# mcat-4cu-b-v2h.net
KiCad netlist of a schematic drawn in EAGLE
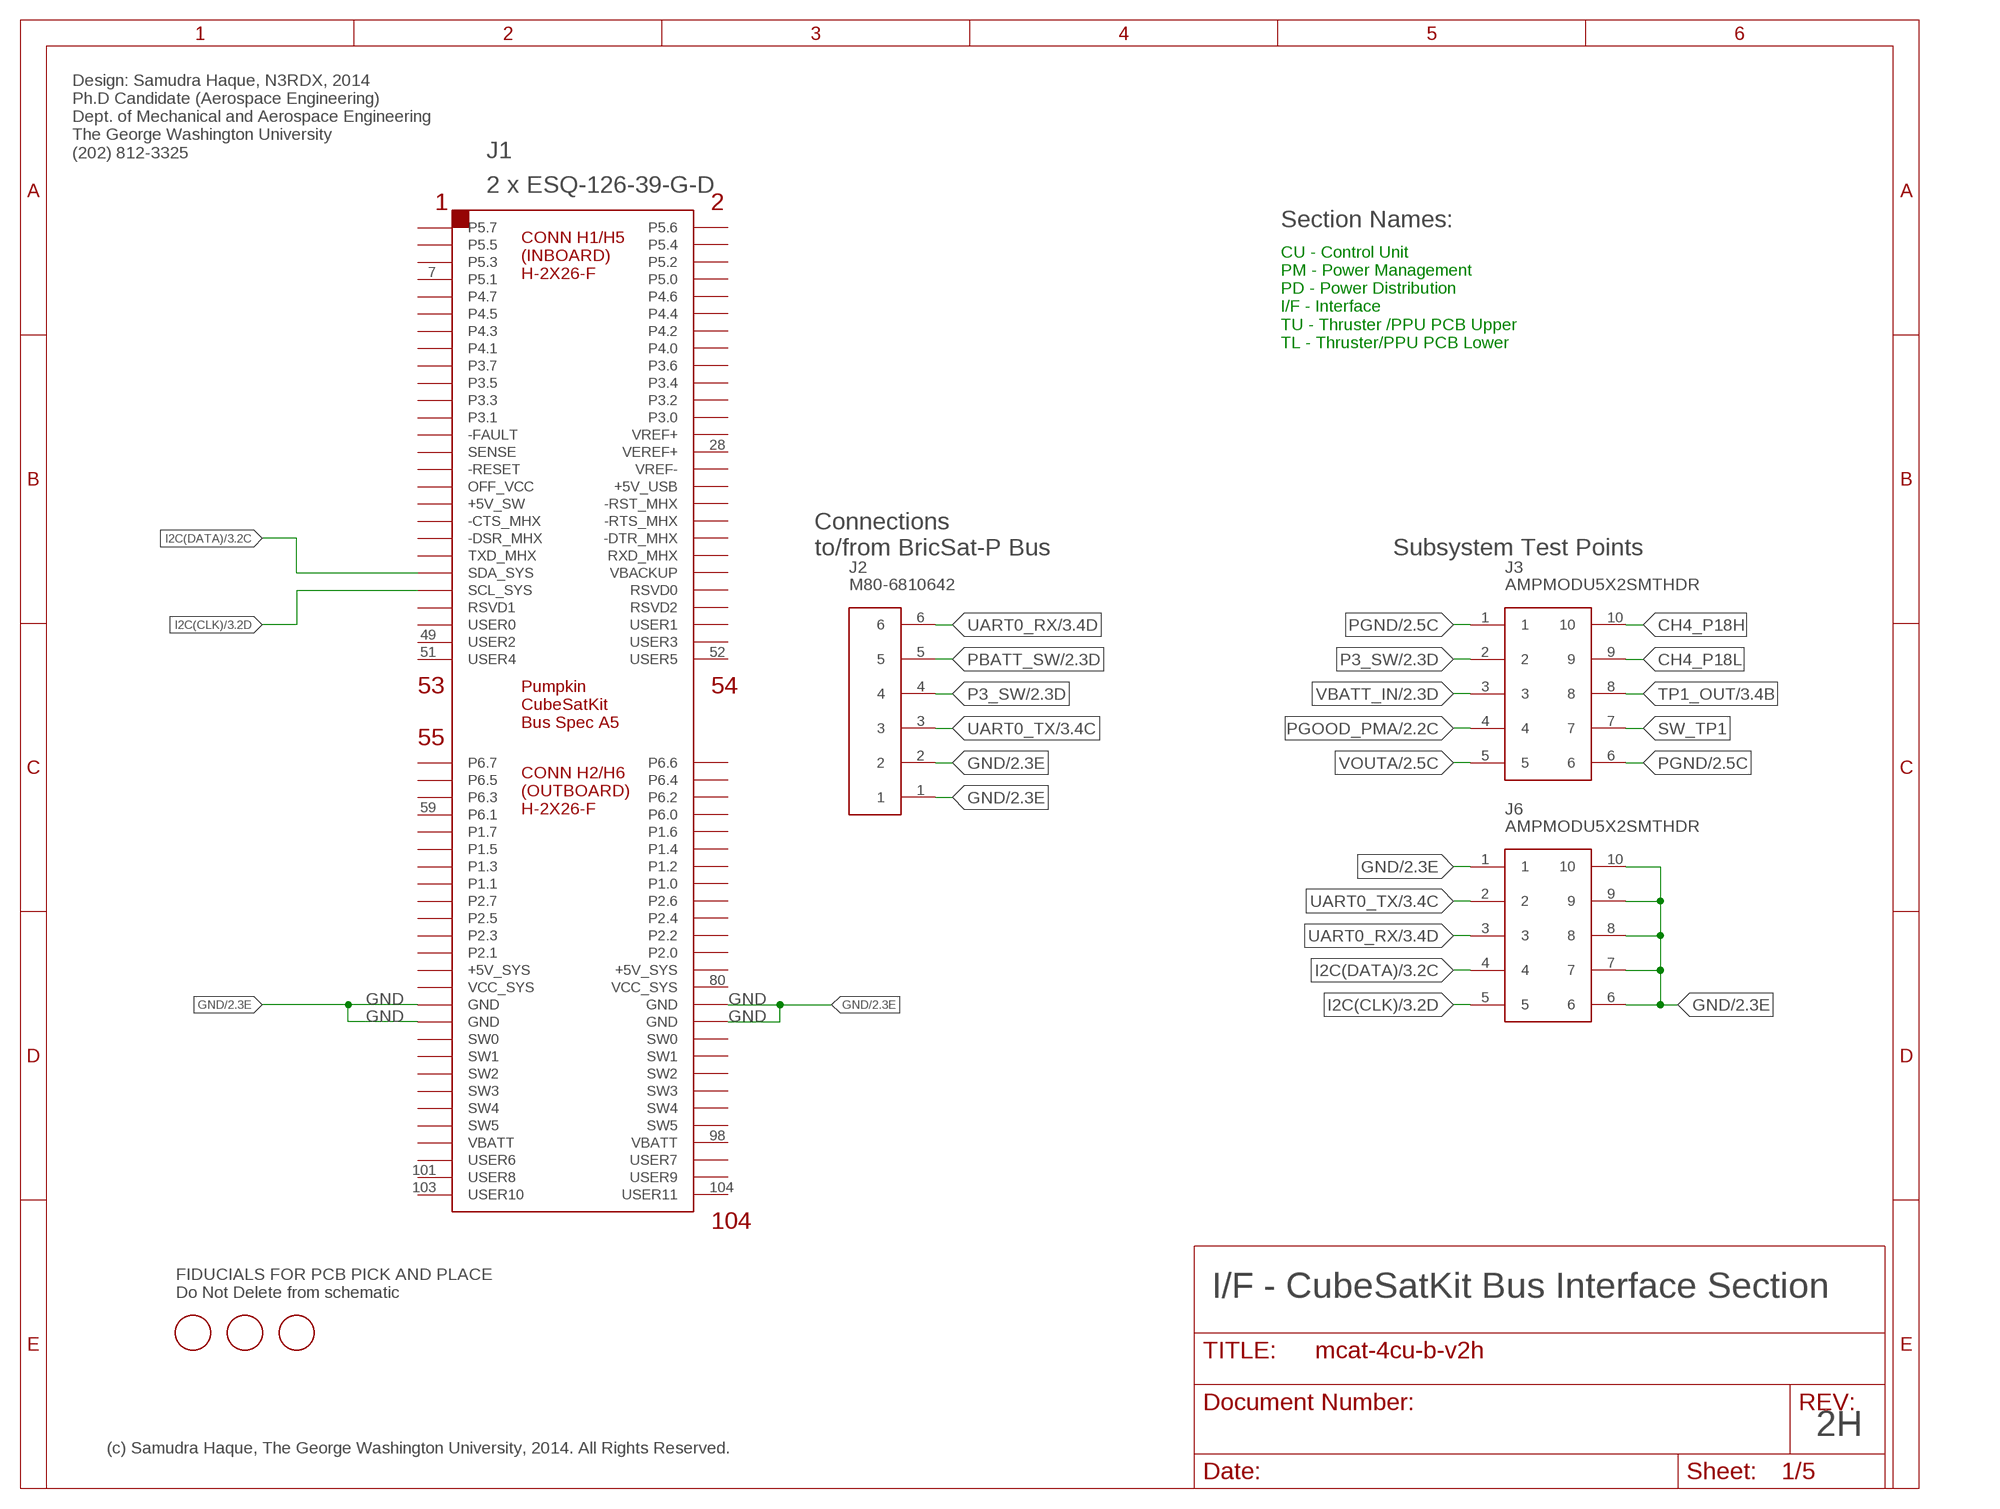
[diagram p0: schematic, sheet 1]
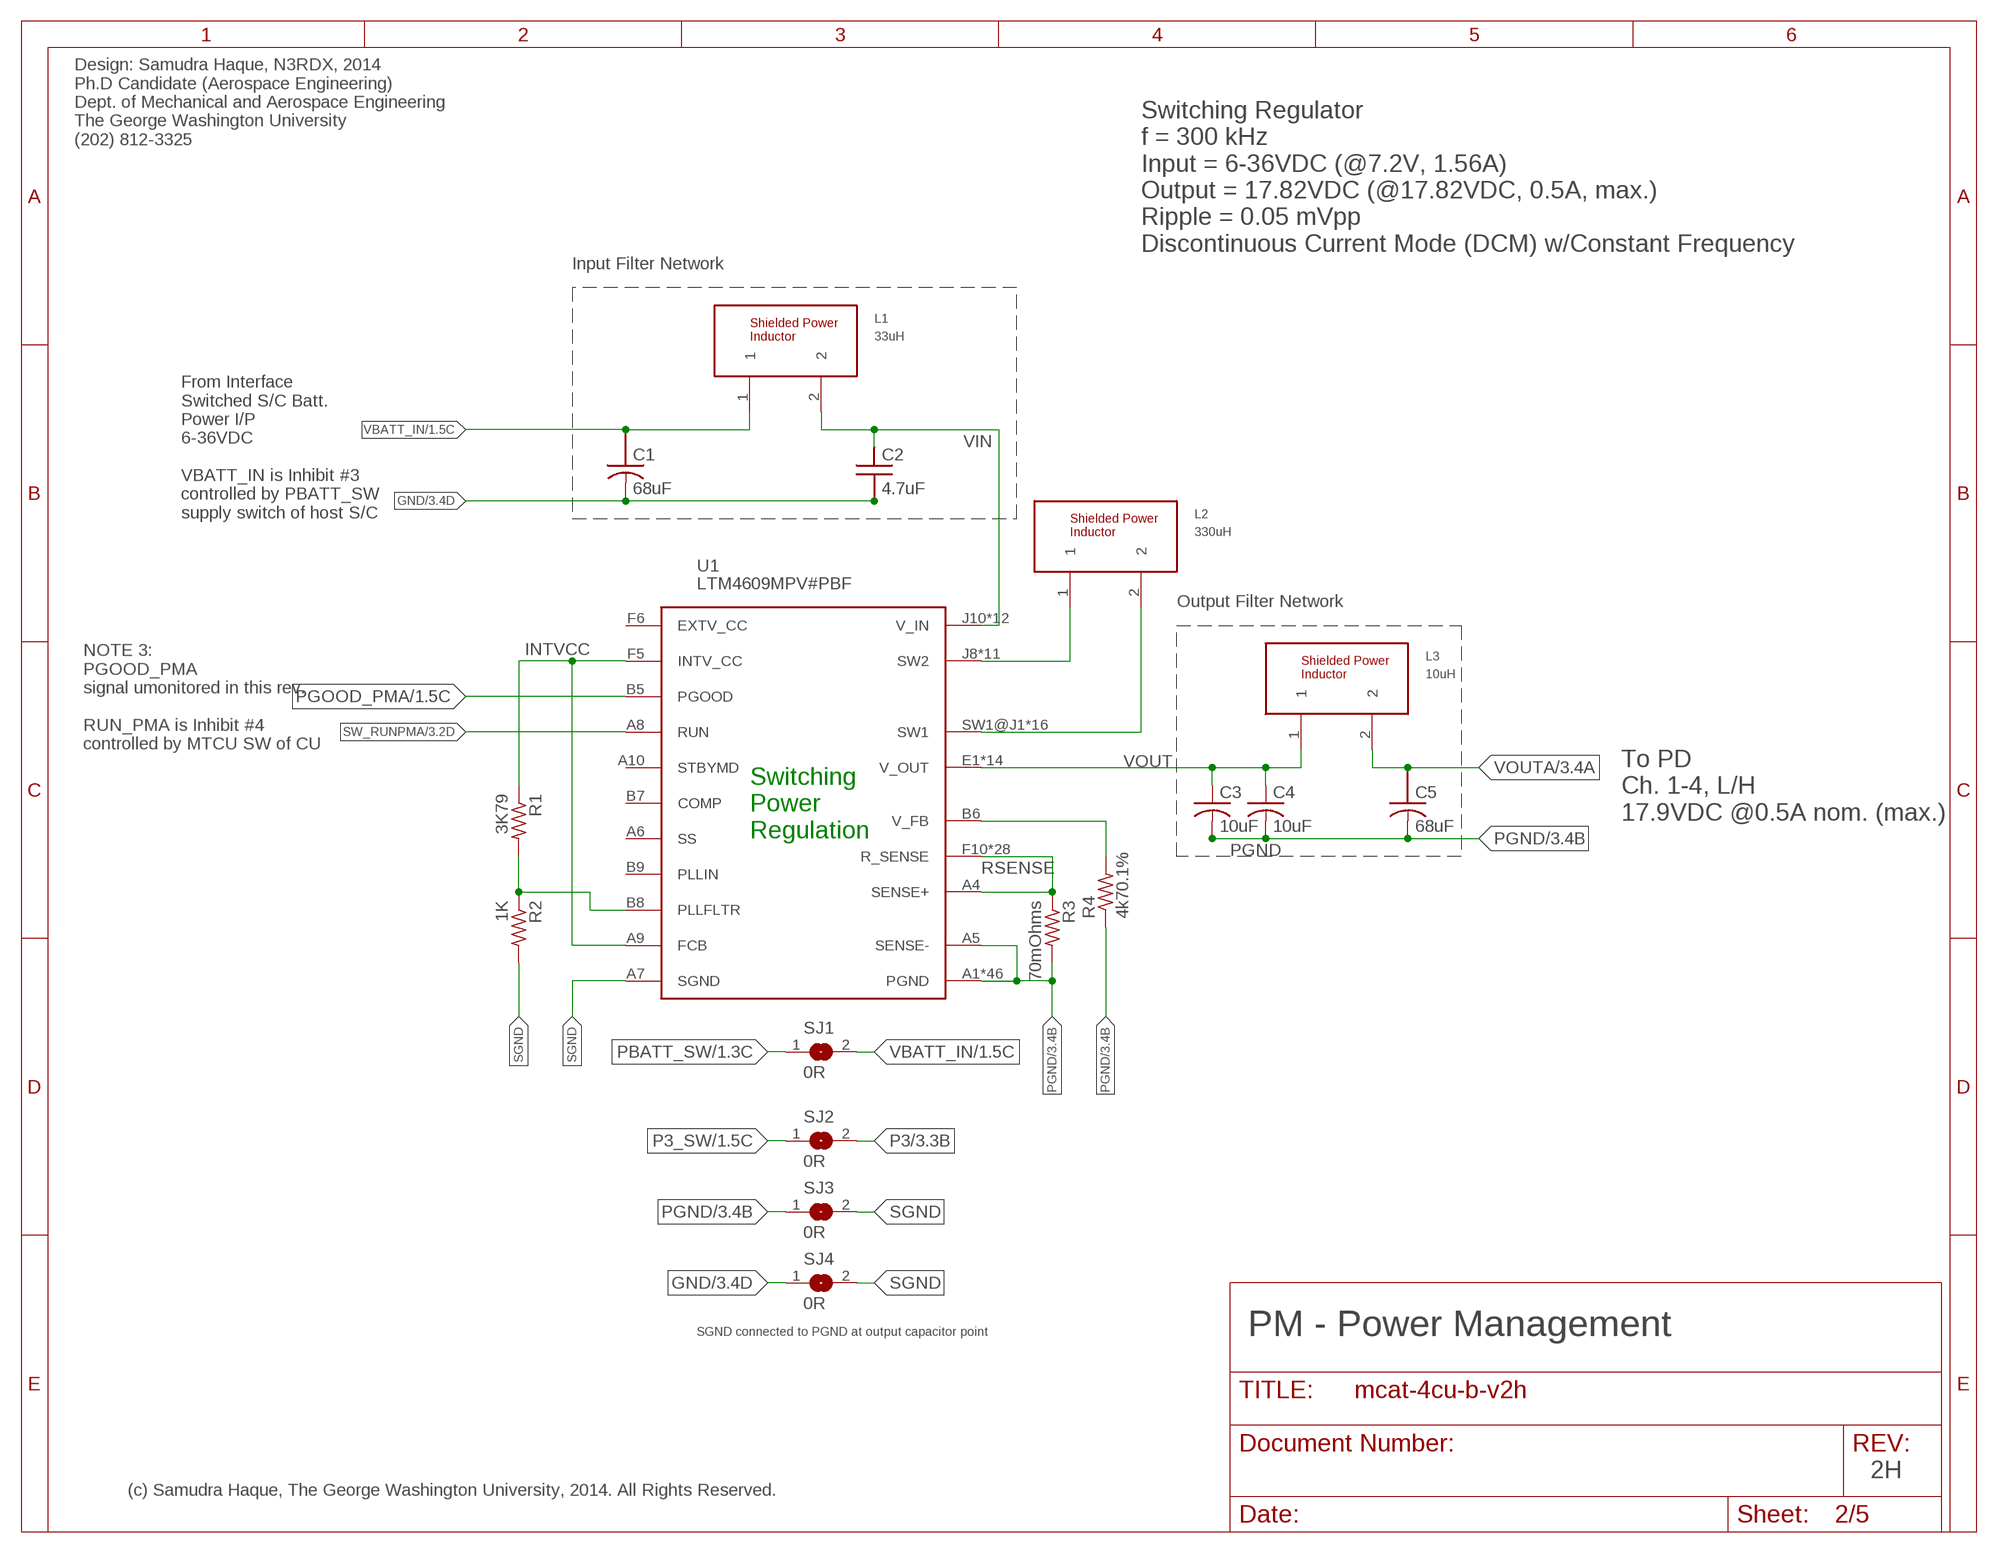
[diagram p1: schematic, sheet 2]
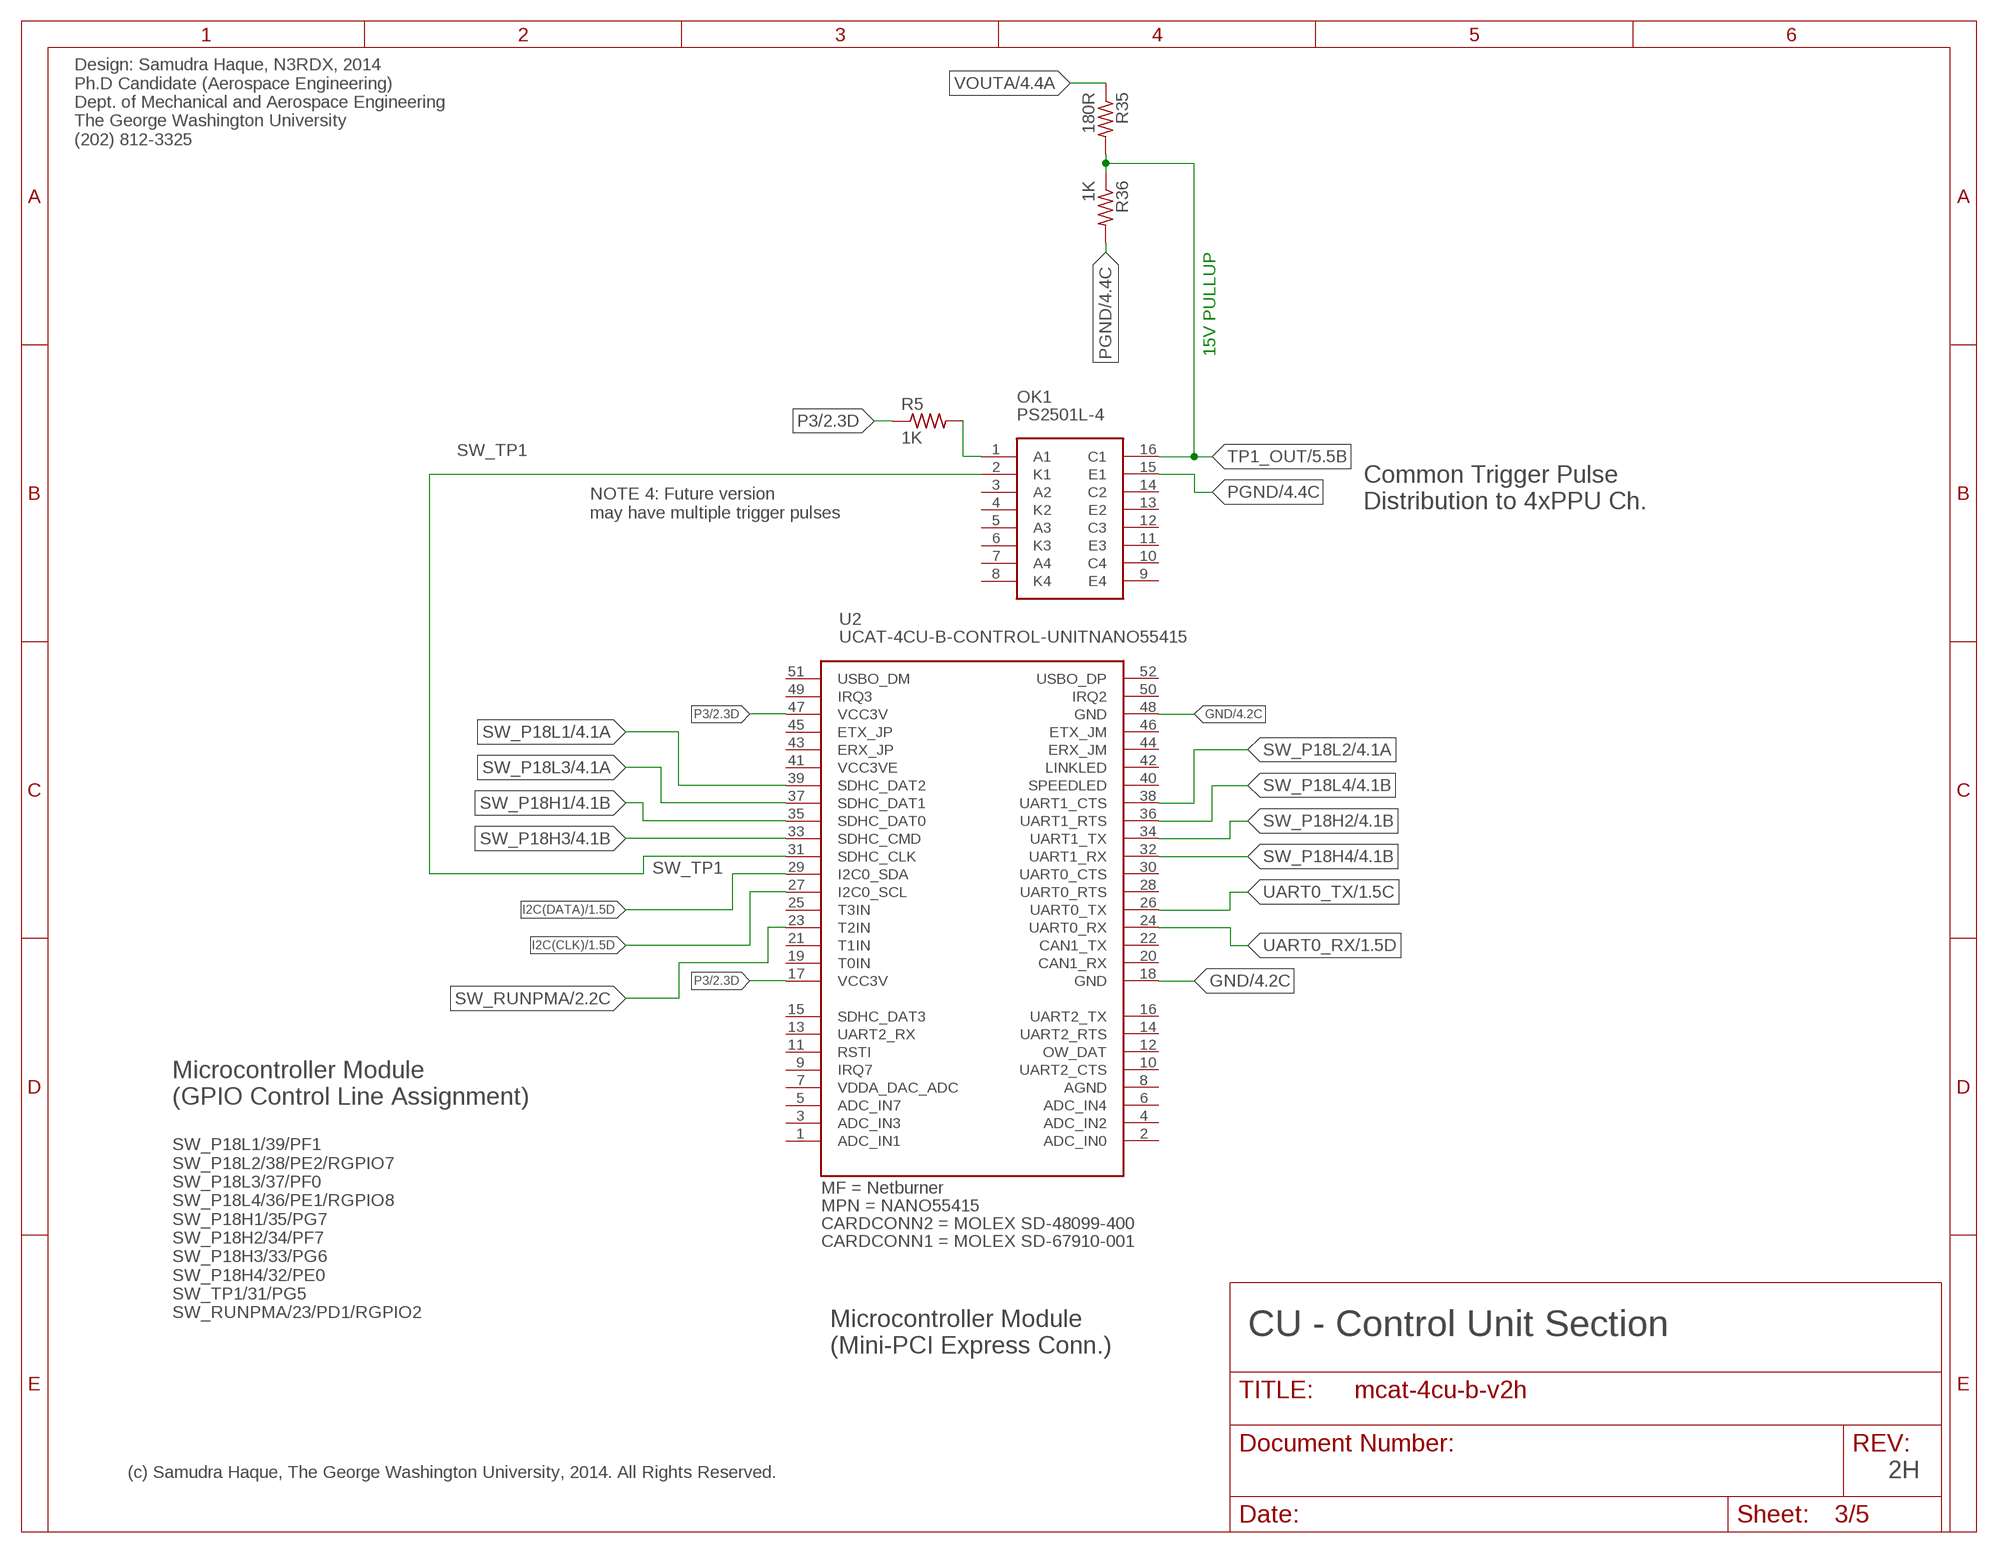
[diagram p2: schematic, sheet 3]
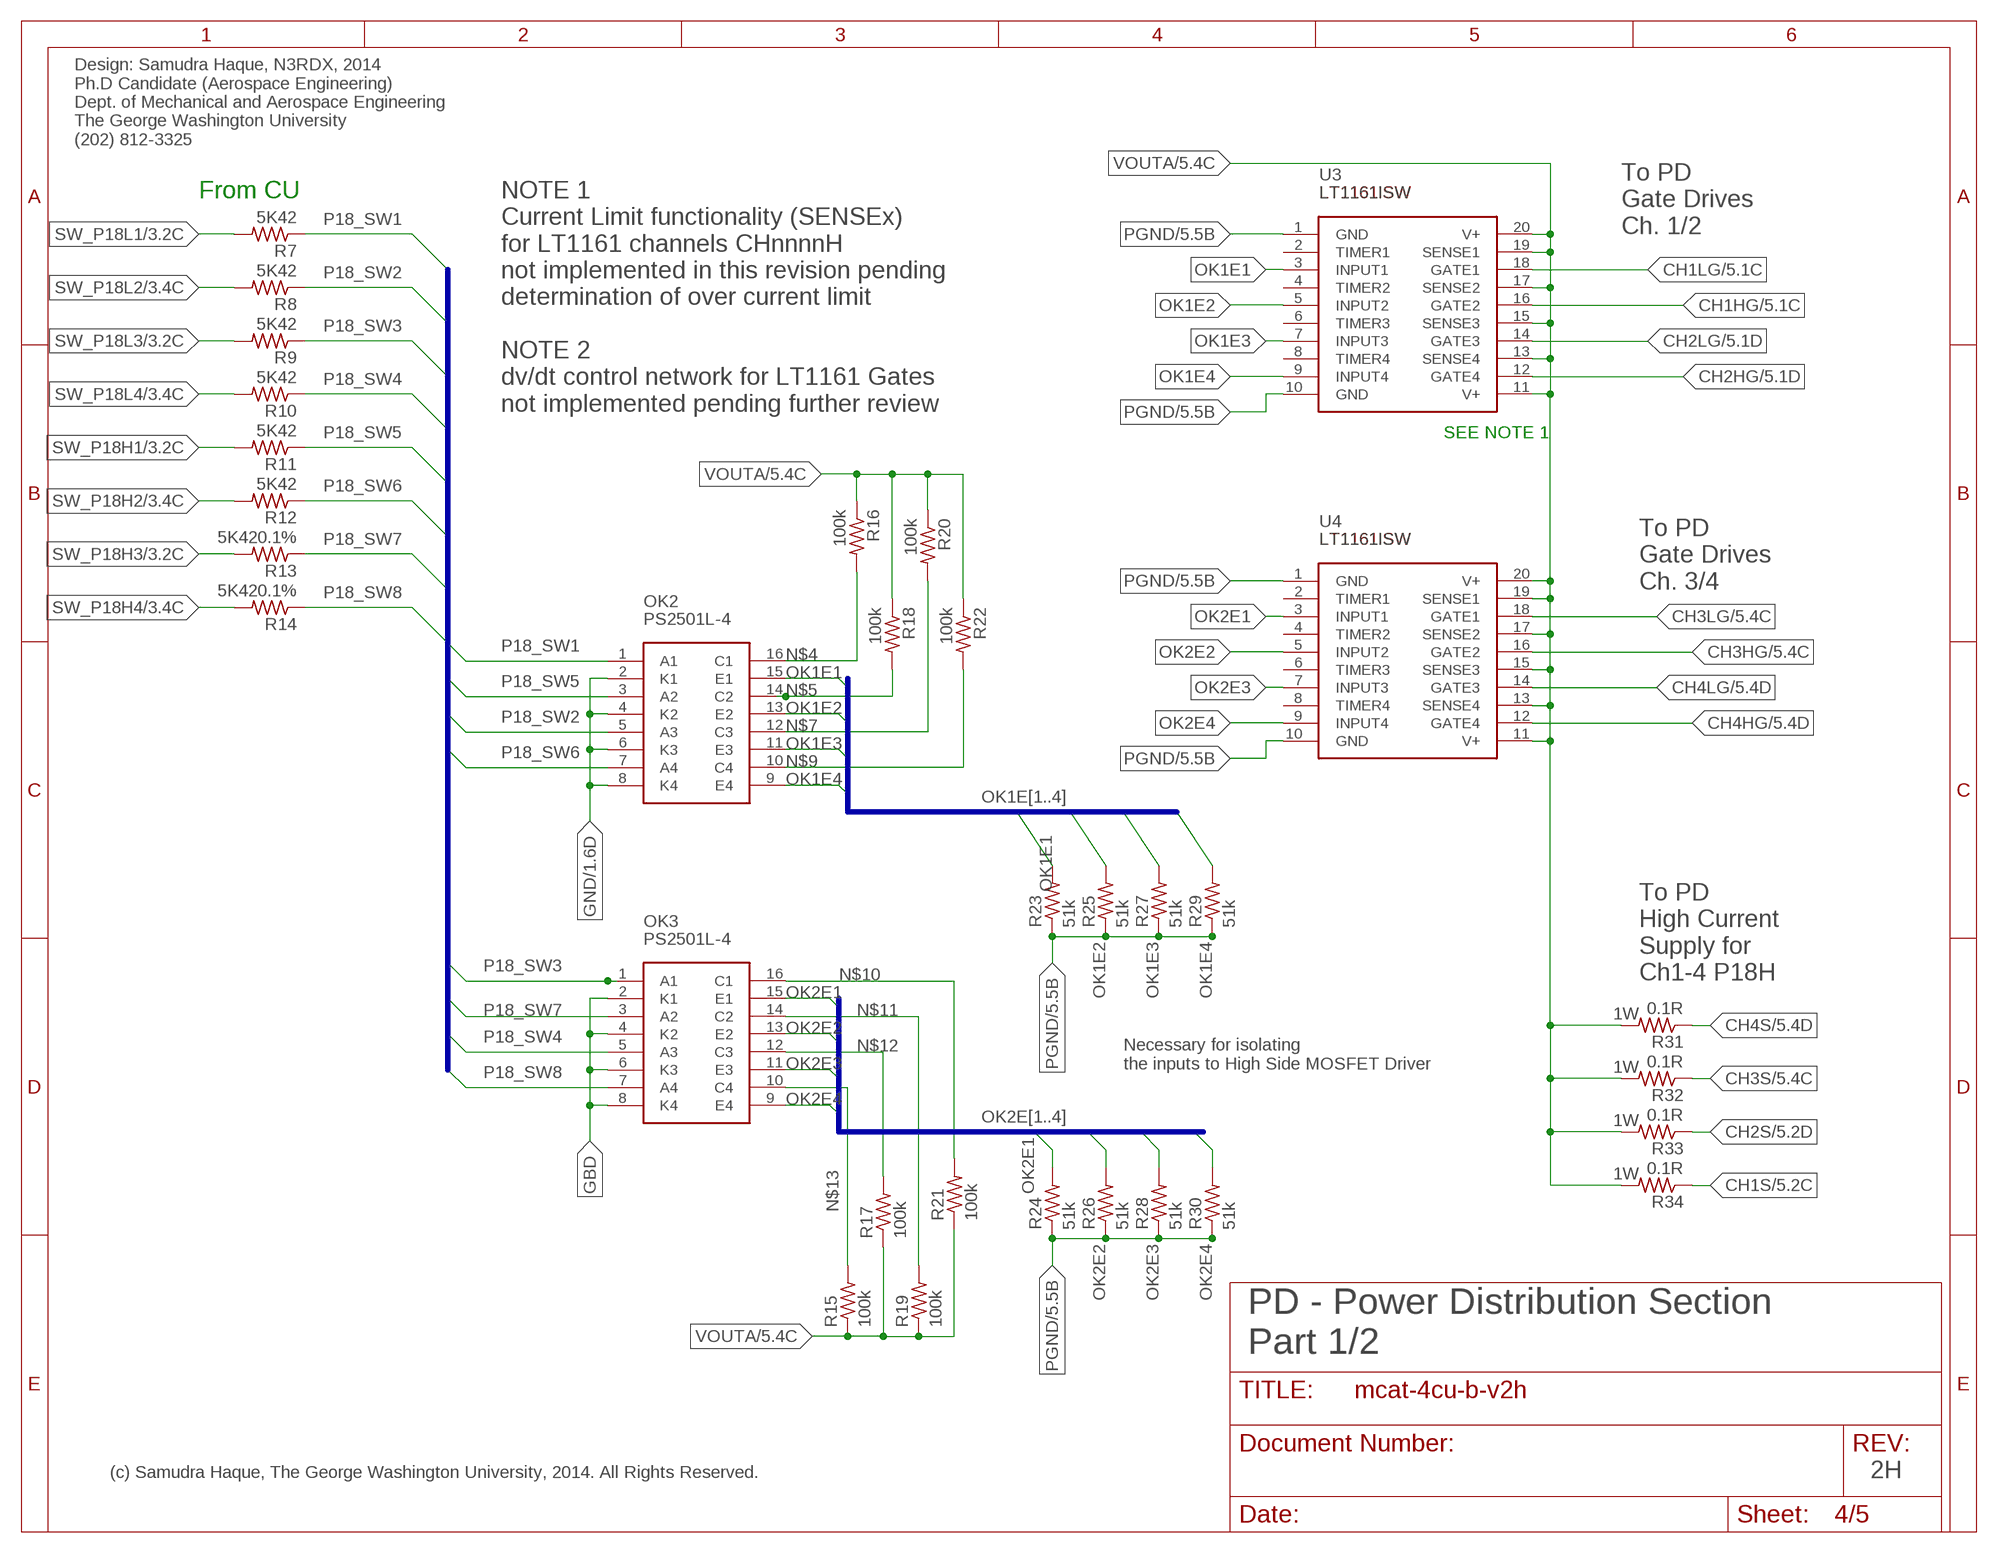
[diagram p3: schematic, sheet 4]
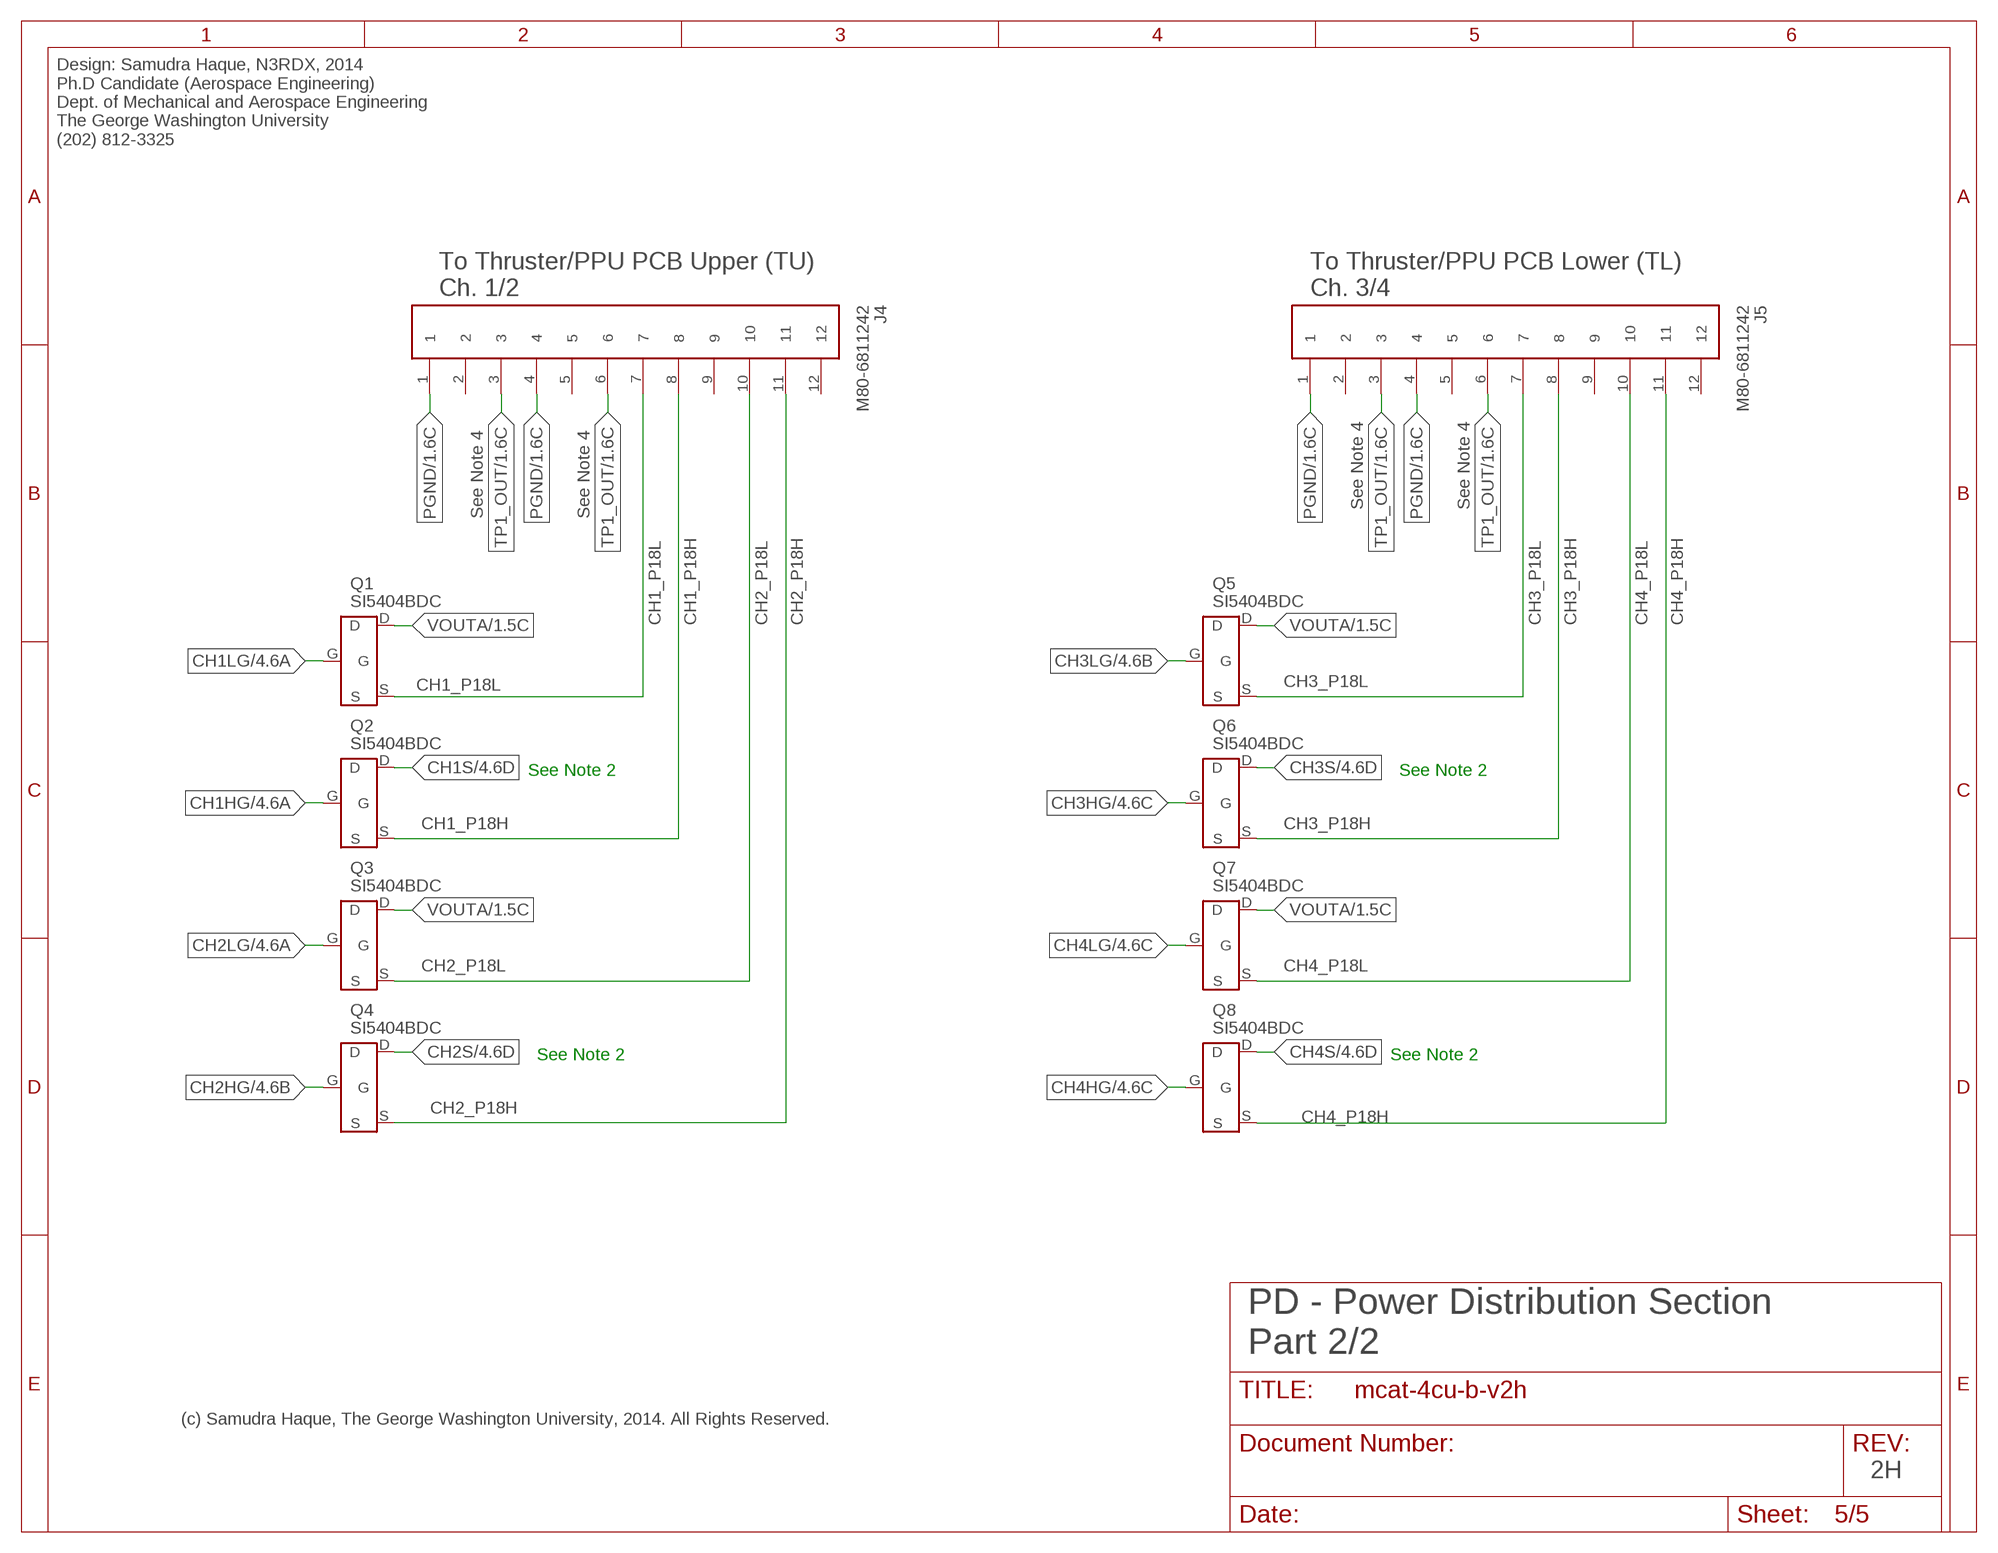
[diagram p4: schematic, sheet 5]

(export (version "E")
  (design (tool "Eeschema 10.0.6"))
  (components
    (comp (ref "OK1")
      (value "PS2501L-4")
      (footprint "eagle-import:PS2501L-4")
      (fields (field (name "MF") "CEL"))
      (libsource (lib "eagle-import") (part "PS2501L-4"))
    )
    (comp (ref "R5")
      (value "1K")
      (footprint "eagle-import:R0805")
      (fields (field (name "MF") "PANASONIC") (field (name "MPN") "ERA-6AEB102V"))
      (libsource (lib "eagle-import") (part "resistor_R-US_R0805"))
    )
    (comp (ref "R35")
      (value "180R")
      (footprint "eagle-import:R0805")
      (fields (field (name "MF") "PANASONIC") (field (name "MPN") "ERA-6AED181V"))
      (libsource (lib "eagle-import") (part "resistor_R-US_R0805"))
    )
    (comp (ref "R36")
      (value "1K")
      (footprint "eagle-import:R0805")
      (fields (field (name "MF") "PANASONIC") (field (name "MPN") "ERA-6AEB102V"))
      (libsource (lib "eagle-import") (part "resistor_R-US_R0805"))
    )
    (comp (ref "U2")
      (value "UCAT-4CU-B-CONTROL-UNITNANO55415")
      (footprint "eagle-import:MOLEX-MINI-PCI-EXPRESS-8MM-52CKT")
      (fields
        (field (name "CARDCONN1") "MOLEX SD-67910-001")
        (field (name "CARDCONN2") "MOLEX SD-48099-400")
        (field (name "MF") "Netburner")
        (field (name "MPN") "NANO55415")
      )
      (libsource (lib "eagle-import") (part "UCAT-4CU-B-CONTROL-UNITNANO55415"))
    )
    (comp (ref "J4")
      (value "M80-6811242")
      (footprint "eagle-import:M80-68112")
      (fields (field (name "MF") "HARWIN"))
      (libsource (lib "eagle-import") (part "M80-6811242"))
    )
    (comp (ref "J5")
      (value "M80-6811242")
      (footprint "eagle-import:M80-68112")
      (fields (field (name "MF") "HARWIN"))
      (libsource (lib "eagle-import") (part "M80-6811242"))
    )
    (comp (ref "Q1")
      (value "SI5404BDC")
      (footprint "eagle-import:1206-8-CHIPFET")
      (fields (field (name "MF") "VISHAY/SILICONIX") (field (name "MPN") "SI5404BDC-T1-E3"))
      (libsource (lib "eagle-import") (part "SI5404BDC"))
    )
    (comp (ref "Q2")
      (value "SI5404BDC")
      (footprint "eagle-import:1206-8-CHIPFET")
      (fields (field (name "MF") "VISHAY/SILICONIX") (field (name "MPN") "SI5404BDC-T1-E3"))
      (libsource (lib "eagle-import") (part "SI5404BDC"))
    )
    (comp (ref "Q3")
      (value "SI5404BDC")
      (footprint "eagle-import:1206-8-CHIPFET")
      (fields (field (name "MF") "VISHAY/SILICONIX") (field (name "MPN") "SI5404BDC-T1-E3"))
      (libsource (lib "eagle-import") (part "SI5404BDC"))
    )
    (comp (ref "Q4")
      (value "SI5404BDC")
      (footprint "eagle-import:1206-8-CHIPFET")
      (fields (field (name "MF") "VISHAY/SILICONIX") (field (name "MPN") "SI5404BDC-T1-E3"))
      (libsource (lib "eagle-import") (part "SI5404BDC"))
    )
    (comp (ref "Q5")
      (value "SI5404BDC")
      (footprint "eagle-import:1206-8-CHIPFET")
      (fields (field (name "MF") "VISHAY/SILICONIX") (field (name "MPN") "SI5404BDC-T1-E3"))
      (libsource (lib "eagle-import") (part "SI5404BDC"))
    )
    (comp (ref "Q6")
      (value "SI5404BDC")
      (footprint "eagle-import:1206-8-CHIPFET")
      (fields (field (name "MF") "VISHAY/SILICONIX") (field (name "MPN") "SI5404BDC-T1-E3"))
      (libsource (lib "eagle-import") (part "SI5404BDC"))
    )
    (comp (ref "Q7")
      (value "SI5404BDC")
      (footprint "eagle-import:1206-8-CHIPFET")
      (fields (field (name "MF") "VISHAY/SILICONIX") (field (name "MPN") "SI5404BDC-T1-E3"))
      (libsource (lib "eagle-import") (part "SI5404BDC"))
    )
    (comp (ref "Q8")
      (value "SI5404BDC")
      (footprint "eagle-import:1206-8-CHIPFET")
      (fields (field (name "MF") "VISHAY/SILICONIX") (field (name "MPN") "SI5404BDC-T1-E3"))
      (libsource (lib "eagle-import") (part "SI5404BDC"))
    )
    (comp (ref "OK2")
      (value "PS2501L-4")
      (footprint "eagle-import:PS2501L-4")
      (fields (field (name "MF") "CEL"))
      (libsource (lib "eagle-import") (part "PS2501L-4"))
    )
    (comp (ref "OK3")
      (value "PS2501L-4")
      (footprint "eagle-import:PS2501L-4")
      (fields (field (name "MF") "CEL"))
      (libsource (lib "eagle-import") (part "PS2501L-4"))
    )
    (comp (ref "R7")
      (value "5K42")
      (footprint "eagle-import:R0805")
      (fields (field (name "MF") "VISHAY") (field (name "MPN") "TNPW08055K42BEEA"))
      (libsource (lib "eagle-import") (part "resistor_R-US_R0805"))
    )
    (comp (ref "R8")
      (value "5K42")
      (footprint "eagle-import:R0805")
      (fields (field (name "MF") "VISHAY") (field (name "MPN") "TNPW08055K42BEEA"))
      (libsource (lib "eagle-import") (part "resistor_R-US_R0805"))
    )
    (comp (ref "R9")
      (value "5K42")
      (footprint "eagle-import:R0805")
      (fields (field (name "MF") "VISHAY") (field (name "MPN") "TNPW08055K42BEEA"))
      (libsource (lib "eagle-import") (part "resistor_R-US_R0805"))
    )
    (comp (ref "R10")
      (value "5K42")
      (footprint "eagle-import:R0805")
      (fields (field (name "MF") "VISHAY") (field (name "MPN") "TNPW08055K42BEEA"))
      (libsource (lib "eagle-import") (part "resistor_R-US_R0805"))
    )
    (comp (ref "R11")
      (value "5K42")
      (footprint "eagle-import:R0805")
      (fields (field (name "MF") "VISHAY") (field (name "MPN") "TNPW08055K42BEEA"))
      (libsource (lib "eagle-import") (part "resistor_R-US_R0805"))
    )
    (comp (ref "R12")
      (value "5K42")
      (footprint "eagle-import:R0805")
      (fields (field (name "MF") "VISHAY") (field (name "MPN") "TNPW08055K42BEEA"))
      (libsource (lib "eagle-import") (part "resistor_R-US_R0805"))
    )
    (comp (ref "R13")
      (value "5K420.1%")
      (footprint "eagle-import:R0805")
      (fields (field (name "MF") "VISHAY") (field (name "MPN") "TNPW08055K42BEEA"))
      (libsource (lib "eagle-import") (part "resistor_R-US_R0805"))
    )
    (comp (ref "R14")
      (value "5K420.1%")
      (footprint "eagle-import:R0805")
      (fields (field (name "MF") "VISHAY") (field (name "MPN") "TNPW08055K42BEEA"))
      (libsource (lib "eagle-import") (part "resistor_R-US_R0805"))
    )
    (comp (ref "R15")
      (value "100k")
      (footprint "eagle-import:R0402")
      (fields (field (name "MF") "YAGEO") (field (name "MPN") "RT0402BRD07100KL"))
      (libsource (lib "eagle-import") (part "resistor_R-US_R0402"))
    )
    (comp (ref "R16")
      (value "100k")
      (footprint "eagle-import:R0402")
      (fields (field (name "MF") "YAGEO") (field (name "MPN") "RT0402BRD07100KL"))
      (libsource (lib "eagle-import") (part "resistor_R-US_R0402"))
    )
    (comp (ref "R17")
      (value "100k")
      (footprint "eagle-import:R0402")
      (fields (field (name "MF") "YAGEO") (field (name "MPN") "RT0402BRD07100KL"))
      (libsource (lib "eagle-import") (part "resistor_R-US_R0402"))
    )
    (comp (ref "R18")
      (value "100k")
      (footprint "eagle-import:R0402")
      (fields (field (name "MF") "YAGEO") (field (name "MPN") "RT0402BRD07100KL"))
      (libsource (lib "eagle-import") (part "resistor_R-US_R0402"))
    )
    (comp (ref "R19")
      (value "100k")
      (footprint "eagle-import:R0402")
      (fields (field (name "MF") "YAGEO") (field (name "MPN") "RT0402BRD07100KL"))
      (libsource (lib "eagle-import") (part "resistor_R-US_R0402"))
    )
    (comp (ref "R20")
      (value "100k")
      (footprint "eagle-import:R0402")
      (fields (field (name "MF") "YAGEO") (field (name "MPN") "RT0402BRD07100KL"))
      (libsource (lib "eagle-import") (part "resistor_R-US_R0402"))
    )
    (comp (ref "R21")
      (value "100k")
      (footprint "eagle-import:R0402")
      (fields (field (name "MF") "YAGEO") (field (name "MPN") "RT0402BRD07100KL"))
      (libsource (lib "eagle-import") (part "resistor_R-US_R0402"))
    )
    (comp (ref "R22")
      (value "100k")
      (footprint "eagle-import:R0402")
      (fields (field (name "MF") "YAGEO") (field (name "MPN") "RT0402BRD07100KL"))
      (libsource (lib "eagle-import") (part "resistor_R-US_R0402"))
    )
    (comp (ref "R23")
      (value "51k")
      (footprint "eagle-import:R0603")
      (fields (field (name "MF") "SUSUMU") (field (name "MPN") "RG1608P-513-B-T5 "))
      (libsource (lib "eagle-import") (part "resistor_R-US_R0603"))
    )
    (comp (ref "R24")
      (value "51k")
      (footprint "eagle-import:R0603")
      (fields (field (name "MF") "SUSUMU") (field (name "MPN") "RG1608P-513-B-T5"))
      (libsource (lib "eagle-import") (part "resistor_R-US_R0603"))
    )
    (comp (ref "R25")
      (value "51k")
      (footprint "eagle-import:R0603")
      (fields (field (name "MF") "SUSUMU") (field (name "MPN") "RG1608P-513-B-T5 "))
      (libsource (lib "eagle-import") (part "resistor_R-US_R0603"))
    )
    (comp (ref "R26")
      (value "51k")
      (footprint "eagle-import:R0603")
      (fields (field (name "MF") "SUSUMU") (field (name "MPN") "RG1608P-513-B-T5"))
      (libsource (lib "eagle-import") (part "resistor_R-US_R0603"))
    )
    (comp (ref "R27")
      (value "51k")
      (footprint "eagle-import:R0603")
      (fields (field (name "MF") "SUSUMU") (field (name "MPN") "RG1608P-513-B-T5"))
      (libsource (lib "eagle-import") (part "resistor_R-US_R0603"))
    )
    (comp (ref "R28")
      (value "51k")
      (footprint "eagle-import:R0603")
      (fields (field (name "MF") "SUSUMU") (field (name "MPN") "RG1608P-513-B-T5"))
      (libsource (lib "eagle-import") (part "resistor_R-US_R0603"))
    )
    (comp (ref "R29")
      (value "51k")
      (footprint "eagle-import:R0603")
      (fields (field (name "MF") "SUSUMU") (field (name "MPN") "RG1608P-513-B-T5"))
      (libsource (lib "eagle-import") (part "resistor_R-US_R0603"))
    )
    (comp (ref "R30")
      (value "51k")
      (footprint "eagle-import:R0603")
      (fields (field (name "MF") "SUSUMU") (field (name "MPN") "RG1608P-513-B-T5"))
      (libsource (lib "eagle-import") (part "resistor_R-US_R0603"))
    )
    (comp (ref "R31")
      (value "0.1R")
      (footprint "eagle-import:R1206")
      (fields
        (field (name "MF") "SUSUMU")
        (field (name "MPN") "PRL1632-R100-F-T1")
        (field (name "RATING") "1W")
      )
      (libsource (lib "eagle-import") (part "R-US_R1206"))
    )
    (comp (ref "R32")
      (value "0.1R")
      (footprint "eagle-import:R1206")
      (fields
        (field (name "MF") "SUSUMU")
        (field (name "MPN") "PRL1632-R100-F-T1")
        (field (name "RATING") "1W")
      )
      (libsource (lib "eagle-import") (part "R-US_R1206"))
    )
    (comp (ref "R33")
      (value "0.1R")
      (footprint "eagle-import:R1206")
      (fields
        (field (name "MF") "SUSUMU")
        (field (name "MPN") "PRL1632-R100-F-T1")
        (field (name "RATING") "1W")
      )
      (libsource (lib "eagle-import") (part "R-US_R1206"))
    )
    (comp (ref "R34")
      (value "0.1R")
      (footprint "eagle-import:R1206")
      (fields
        (field (name "MF") "SUSUMU")
        (field (name "MPN") "PRL1632-R100-F-T1")
        (field (name "RATING") "1W")
      )
      (libsource (lib "eagle-import") (part "R-US_R1206"))
    )
    (comp (ref "U3")
      (value "LT1161ISW")
      (footprint "eagle-import:20-LEAD-PLASTIC-SO")
      (fields (field (name "MF") "LINEAR") (field (name "MPN") "LT1161ISW#TRPBF"))
      (libsource (lib "eagle-import") (part "LT1161ISW"))
    )
    (comp (ref "U4")
      (value "LT1161ISW")
      (footprint "eagle-import:20-LEAD-PLASTIC-SO")
      (fields (field (name "MF") "LINEAR") (field (name "MPN") "LT1161ISW#TRPBF"))
      (libsource (lib "eagle-import") (part "LT1161ISW"))
    )
    (comp (ref "C1")
      (value "68uF")
      (footprint "eagle-import:OS-CON-SVPF-F12")
      (fields (field (name "MF") "OSCON") (field (name "MPN") "50SVPF68M"))
      (libsource (lib "eagle-import") (part "OSCON-50SVPF68M"))
    )
    (comp (ref "C2")
      (value "4.7uF")
      (footprint "eagle-import:MLCC-X7R-1210")
      (fields (field (name "MF") "AVX") (field (name "MPN") "LD105C475KAB2A"))
      (libsource (lib "eagle-import") (part "AVX-LD105C475KAB2A"))
    )
    (comp (ref "C3")
      (value "10uF")
      (footprint "eagle-import:C1210K")
      (fields (field (name "MF") "MURATA") (field (name "MPN") "GRM32ER71H106KA12L"))
      (libsource (lib "eagle-import") (part "C-USC1210K"))
    )
    (comp (ref "C4")
      (value "10uF")
      (footprint "eagle-import:C1210K")
      (fields (field (name "MF") "MURATA") (field (name "MPN") "GRM32ER71H106KA12L"))
      (libsource (lib "eagle-import") (part "C-USC1210K"))
    )
    (comp (ref "C5")
      (value "68uF")
      (footprint "eagle-import:OS-CON-SVPF-F12")
      (fields (field (name "MF") "OSCON") (field (name "MPN") "50SVPF68M"))
      (libsource (lib "eagle-import") (part "OSCON-50SVPF68M"))
    )
    (comp (ref "L1")
      (value "33uH")
      (footprint "eagle-import:MSS1048")
      (fields (field (name "MF") "COILCRAFT") (field (name "MPN") "MSS1038-333ML_"))
      (libsource (lib "eagle-import") (part "MSS1038-333ML_"))
    )
    (comp (ref "L2")
      (value "330uH")
      (footprint "eagle-import:MSS1048")
      (fields (field (name "MF") "COILCRAFT") (field (name "MPN") "MSS1048-334KL_"))
      (libsource (lib "eagle-import") (part "MSS1048-334KL_"))
    )
    (comp (ref "L3")
      (value "10uH")
      (footprint "eagle-import:SERIES-POWER-INDUCTORS")
      (fields (field (name "MF") "PANASONIC") (field (name "MPN") "ELL5PS100M"))
      (libsource (lib "eagle-import") (part "ELL-5PS100M"))
    )
    (comp (ref "R1")
      (value "3K79")
      (footprint "eagle-import:R0805")
      (fields (field (name "MF") "VISHAY") (field (name "MPN") "PAT0805E3791BST1"))
      (libsource (lib "eagle-import") (part "R-US_R0805"))
    )
    (comp (ref "R2")
      (value "1K")
      (footprint "eagle-import:R0805")
      (fields (field (name "MF") "VISHAY") (field (name "MPN") "PAT0805E1001BST1"))
      (libsource (lib "eagle-import") (part "R-US_R0805"))
    )
    (comp (ref "R3")
      (value "70mOhms")
      (footprint "eagle-import:R1206")
      (fields (field (name "MF") "VISHAY") (field (name "MPN") "WSL1206R0700FEB18"))
      (libsource (lib "eagle-import") (part "resistor_R-US_R1206"))
    )
    (comp (ref "R4")
      (value "4k70.1%")
      (footprint "eagle-import:R0603")
      (fields (field (name "MF") "SUSUMU") (field (name "MPN") "RG1608P-472-B-T5"))
      (libsource (lib "eagle-import") (part "resistor_R-US_R0603"))
    )
    (comp (ref "SJ1") (value "0R") (footprint "eagle-import:SJ") (libsource (lib "eagle-import") (part "SJ")))
    (comp (ref "SJ2") (value "0R") (footprint "eagle-import:SJ") (libsource (lib "eagle-import") (part "SJ")))
    (comp (ref "SJ3") (value "0R") (footprint "eagle-import:SJ") (libsource (lib "eagle-import") (part "SJ")))
    (comp (ref "SJ4") (value "0R") (footprint "eagle-import:SJ") (libsource (lib "eagle-import") (part "SJ")))
    (comp (ref "U1")
      (value "LTM4609MPV#PBF")
      (footprint "eagle-import:LGA-141-LTC-05-08-1840-B")
      (fields (field (name "MF") "Linear"))
      (libsource (lib "eagle-import") (part "LTM4609MPV#PBFROHS/HITEMP"))
    )
    (comp (ref "FID1")
      (value "FIDUCIAL")
      (footprint "eagle-import:FIDUCIAL_1MM")
      (libsource (lib "eagle-import") (part "FIDUCIAL"))
    )
    (comp (ref "FID2")
      (value "FIDUCIAL")
      (footprint "eagle-import:FIDUCIAL_1MM")
      (libsource (lib "eagle-import") (part "FIDUCIAL"))
    )
    (comp (ref "FID3")
      (value "FIDUCIAL")
      (footprint "eagle-import:FIDUCIAL_1MM")
      (libsource (lib "eagle-import") (part "FIDUCIAL"))
    )
    (comp (ref "J1")
      (value "2 x ESQ-126-39-G-D")
      (footprint "eagle-import:CSK-BUS-PKG")
      (libsource (lib "eagle-import") (part "CSK-BUS-CONN2X2X26"))
    )
    (comp (ref "J2")
      (value "M80-6810642")
      (footprint "eagle-import:M80-68106")
      (fields (field (name "MF") "HARWIN"))
      (libsource (lib "eagle-import") (part "M80-6810642"))
    )
    (comp (ref "J3")
      (value "AMPMODU5X2SMTHDR")
      (footprint "eagle-import:AMPMODU-SMT-PIN-HEADER-5X2")
      (fields (field (name "MF") "AMPMODU") (field (name "MPN") "146131-4"))
      (libsource (lib "eagle-import") (part "AMPMODU-5-146131-X(5X2)"))
    )
    (comp (ref "J6")
      (value "AMPMODU5X2SMTHDR")
      (footprint "eagle-import:AMPMODU-SMT-PIN-HEADER-5X2")
      (fields (field (name "MF") "AMPMODU") (field (name "MPN") "146131-4"))
      (libsource (lib "eagle-import") (part "AMPMODU-5-146131-X(5X2)"))
    )
  )
  (nets
    (net (code "3") (name "CH1HG") (class "Default")
      (node (ref "Q2") (pin "G") (pinfunction "G_G") (pintype "bidirectional"))
      (node (ref "U3") (pin "16") (pinfunction "GATE2_16") (pintype "bidirectional"))
    )
    (net (code "4") (name "CH1LG") (class "Default")
      (node (ref "Q1") (pin "G") (pinfunction "G_G") (pintype "bidirectional"))
      (node (ref "U3") (pin "18") (pinfunction "GATE1_18") (pintype "bidirectional"))
    )
    (net (code "5") (name "CH1S") (class "Default")
      (node (ref "Q2") (pin "D") (pinfunction "D_D") (pintype "bidirectional"))
      (node (ref "R34") (pin "1") (pinfunction "1_1") (pintype "passive"))
    )
    (net (code "6") (name "CH1_P18H") (class "Default")
      (node (ref "J4") (pin "8") (pinfunction "8_8") (pintype "bidirectional"))
      (node (ref "Q2") (pin "S") (pinfunction "S_S") (pintype "bidirectional"))
    )
    (net (code "7") (name "CH1_P18L") (class "Default")
      (node (ref "J4") (pin "7") (pinfunction "7_7") (pintype "bidirectional"))
      (node (ref "Q1") (pin "S") (pinfunction "S_S") (pintype "bidirectional"))
    )
    (net (code "8") (name "CH2HG") (class "Default")
      (node (ref "Q4") (pin "G") (pinfunction "G_G") (pintype "bidirectional"))
      (node (ref "U3") (pin "12") (pinfunction "GATE4_12") (pintype "bidirectional"))
    )
    (net (code "9") (name "CH2LG") (class "Default")
      (node (ref "Q3") (pin "G") (pinfunction "G_G") (pintype "bidirectional"))
      (node (ref "U3") (pin "14") (pinfunction "GATE3_14") (pintype "bidirectional"))
    )
    (net (code "10") (name "CH2S") (class "Default")
      (node (ref "Q4") (pin "D") (pinfunction "D_D") (pintype "bidirectional"))
      (node (ref "R33") (pin "1") (pinfunction "1_1") (pintype "passive"))
    )
    (net (code "11") (name "CH2_P18H") (class "Default")
      (node (ref "J4") (pin "11") (pinfunction "11_11") (pintype "bidirectional"))
      (node (ref "Q4") (pin "S") (pinfunction "S_S") (pintype "bidirectional"))
    )
    (net (code "12") (name "CH2_P18L") (class "Default")
      (node (ref "J4") (pin "10") (pinfunction "10_10") (pintype "bidirectional"))
      (node (ref "Q3") (pin "S") (pinfunction "S_S") (pintype "bidirectional"))
    )
    (net (code "13") (name "CH3HG") (class "Default")
      (node (ref "Q6") (pin "G") (pinfunction "G_G") (pintype "bidirectional"))
      (node (ref "U4") (pin "16") (pinfunction "GATE2_16") (pintype "bidirectional"))
    )
    (net (code "14") (name "CH3LG") (class "Default")
      (node (ref "Q5") (pin "G") (pinfunction "G_G") (pintype "bidirectional"))
      (node (ref "U4") (pin "18") (pinfunction "GATE1_18") (pintype "bidirectional"))
    )
    (net (code "15") (name "CH3S") (class "Default")
      (node (ref "Q6") (pin "D") (pinfunction "D_D") (pintype "bidirectional"))
      (node (ref "R32") (pin "1") (pinfunction "1_1") (pintype "passive"))
    )
    (net (code "16") (name "CH3_P18H") (class "Default")
      (node (ref "J5") (pin "8") (pinfunction "8_8") (pintype "bidirectional"))
      (node (ref "Q6") (pin "S") (pinfunction "S_S") (pintype "bidirectional"))
    )
    (net (code "17") (name "CH3_P18L") (class "Default")
      (node (ref "J5") (pin "7") (pinfunction "7_7") (pintype "bidirectional"))
      (node (ref "Q5") (pin "S") (pinfunction "S_S") (pintype "bidirectional"))
    )
    (net (code "18") (name "CH4HG") (class "Default")
      (node (ref "Q8") (pin "G") (pinfunction "G_G") (pintype "bidirectional"))
      (node (ref "U4") (pin "12") (pinfunction "GATE4_12") (pintype "bidirectional"))
    )
    (net (code "19") (name "CH4LG") (class "Default")
      (node (ref "Q7") (pin "G") (pinfunction "G_G") (pintype "bidirectional"))
      (node (ref "U4") (pin "14") (pinfunction "GATE3_14") (pintype "bidirectional"))
    )
    (net (code "20") (name "CH4S") (class "Default")
      (node (ref "Q8") (pin "D") (pinfunction "D_D") (pintype "bidirectional"))
      (node (ref "R31") (pin "1") (pinfunction "1_1") (pintype "passive"))
    )
    (net (code "21") (name "CH4_P18H") (class "Default")
      (node (ref "J3") (pin "10") (pinfunction "10_10") (pintype "bidirectional"))
      (node (ref "J5") (pin "11") (pinfunction "11_11") (pintype "bidirectional"))
      (node (ref "Q8") (pin "S") (pinfunction "S_S") (pintype "bidirectional"))
    )
    (net (code "22") (name "CH4_P18L") (class "Default")
      (node (ref "J3") (pin "9") (pinfunction "9_9") (pintype "bidirectional"))
      (node (ref "J5") (pin "10") (pinfunction "10_10") (pintype "bidirectional"))
      (node (ref "Q7") (pin "S") (pinfunction "S_S") (pintype "bidirectional"))
    )
    (net (code "23") (name "GBD") (class "Default")
      (node (ref "OK3") (pin "2") (pinfunction "K1_2") (pintype "bidirectional"))
      (node (ref "OK3") (pin "4") (pinfunction "K2_4") (pintype "bidirectional"))
      (node (ref "OK3") (pin "6") (pinfunction "K3_6") (pintype "bidirectional"))
      (node (ref "OK3") (pin "8") (pinfunction "K4_8") (pintype "bidirectional"))
    )
    (net (code "24") (name "GND") (class "Default")
      (node (ref "C1") (pin "K1") (pinfunction "K_K1") (pintype "passive"))
      (node (ref "C2") (pin "2") (pinfunction "2_2") (pintype "passive"))
      (node (ref "J1") (pin "81") (pinfunction "GND_81") (pintype "bidirectional"))
      (node (ref "J1") (pin "82") (pinfunction "GND_82") (pintype "bidirectional"))
      (node (ref "J1") (pin "83") (pinfunction "GND_83") (pintype "bidirectional"))
      (node (ref "J1") (pin "84") (pinfunction "GND_84") (pintype "bidirectional"))
      (node (ref "J2") (pin "1") (pinfunction "1_1") (pintype "bidirectional"))
      (node (ref "J2") (pin "2") (pinfunction "2_2") (pintype "bidirectional"))
      (node (ref "J6") (pin "1") (pinfunction "1_1") (pintype "bidirectional"))
      (node (ref "J6") (pin "10") (pinfunction "10_10") (pintype "bidirectional"))
      (node (ref "J6") (pin "6") (pinfunction "6_6") (pintype "bidirectional"))
      (node (ref "J6") (pin "7") (pinfunction "7_7") (pintype "bidirectional"))
      (node (ref "J6") (pin "8") (pinfunction "8_8") (pintype "bidirectional"))
      (node (ref "J6") (pin "9") (pinfunction "9_9") (pintype "bidirectional"))
      (node (ref "OK2") (pin "2") (pinfunction "K1_2") (pintype "bidirectional"))
      (node (ref "OK2") (pin "4") (pinfunction "K2_4") (pintype "bidirectional"))
      (node (ref "OK2") (pin "6") (pinfunction "K3_6") (pintype "bidirectional"))
      (node (ref "OK2") (pin "8") (pinfunction "K4_8") (pintype "bidirectional"))
      (node (ref "SJ4") (pin "1") (pinfunction "1_1") (pintype "passive"))
      (node (ref "U2") (pin "18") (pinfunction "GND_18") (pintype "bidirectional"))
      (node (ref "U2") (pin "48") (pinfunction "GND_48") (pintype "bidirectional"))
    )
    (net (code "25") (name "I2C(CLK)") (class "Default")
      (node (ref "J1") (pin "43") (pinfunction "SCL_SYS_43") (pintype "bidirectional"))
      (node (ref "J6") (pin "5") (pinfunction "5_5") (pintype "bidirectional"))
      (node (ref "U2") (pin "27") (pinfunction "I2C0_SCL_27") (pintype "bidirectional"))
    )
    (net (code "26") (name "I2C(DATA)") (class "Default")
      (node (ref "J1") (pin "41") (pinfunction "SDA_SYS_41") (pintype "bidirectional"))
      (node (ref "J6") (pin "4") (pinfunction "4_4") (pintype "bidirectional"))
      (node (ref "U2") (pin "29") (pinfunction "I2C0_SDA_29") (pintype "bidirectional"))
    )
    (net (code "27") (name "INTVCC") (class "Default")
      (node (ref "R1") (pin "1") (pinfunction "1_1") (pintype "passive"))
      (node (ref "U1") (pin "A9") (pinfunction "FCB_A9") (pintype "bidirectional"))
      (node (ref "U1") (pin "F5") (pinfunction "INTV_CC_F5") (pintype "bidirectional"))
    )
    (net (code "28") (name "N$4") (class "Default")
      (node (ref "OK2") (pin "16") (pinfunction "C1_16") (pintype "bidirectional"))
      (node (ref "R16") (pin "2") (pinfunction "2_2") (pintype "passive"))
    )
    (net (code "29") (name "N$5") (class "Default")
      (node (ref "OK2") (pin "14") (pinfunction "C2_14") (pintype "bidirectional"))
      (node (ref "R18") (pin "2") (pinfunction "2_2") (pintype "passive"))
    )
    (net (code "30") (name "N$7") (class "Default")
      (node (ref "OK2") (pin "12") (pinfunction "C3_12") (pintype "bidirectional"))
      (node (ref "R20") (pin "2") (pinfunction "2_2") (pintype "passive"))
    )
    (net (code "31") (name "N$9") (class "Default")
      (node (ref "OK2") (pin "10") (pinfunction "C4_10") (pintype "bidirectional"))
      (node (ref "R22") (pin "2") (pinfunction "2_2") (pintype "passive"))
    )
    (net (code "32") (name "N$10") (class "Default")
      (node (ref "OK3") (pin "16") (pinfunction "C1_16") (pintype "bidirectional"))
      (node (ref "R21") (pin "2") (pinfunction "2_2") (pintype "passive"))
    )
    (net (code "33") (name "N$11") (class "Default")
      (node (ref "OK3") (pin "14") (pinfunction "C2_14") (pintype "bidirectional"))
      (node (ref "R19") (pin "2") (pinfunction "2_2") (pintype "passive"))
    )
    (net (code "34") (name "N$12") (class "Default")
      (node (ref "OK3") (pin "12") (pinfunction "C3_12") (pintype "bidirectional"))
      (node (ref "R17") (pin "2") (pinfunction "2_2") (pintype "passive"))
    )
    (net (code "35") (name "N$13") (class "Default")
      (node (ref "OK3") (pin "10") (pinfunction "C4_10") (pintype "bidirectional"))
      (node (ref "R15") (pin "2") (pinfunction "2_2") (pintype "passive"))
    )
    (net (code "36") (name "Net-(L2-Pad1)") (class "Default")
      (node (ref "L2") (pin "1") (pinfunction "1_1") (pintype "bidirectional"))
      (node (ref "U1") (pin "J8") (pinfunction "SW2_J8") (pintype "bidirectional"))
      (node (ref "U1") (pin "J9") (pinfunction "SW2_J9") (pintype "bidirectional"))
      (node (ref "U1") (pin "K7") (pinfunction "SW2_K7") (pintype "bidirectional"))
      (node (ref "U1") (pin "K8") (pinfunction "SW2_K8") (pintype "bidirectional"))
      (node (ref "U1") (pin "K9") (pinfunction "SW2_K9") (pintype "bidirectional"))
      (node (ref "U1") (pin "L7") (pinfunction "SW2_L7") (pintype "bidirectional"))
      (node (ref "U1") (pin "L8") (pinfunction "SW2_L8") (pintype "bidirectional"))
      (node (ref "U1") (pin "L9") (pinfunction "SW2_L9") (pintype "bidirectional"))
      (node (ref "U1") (pin "M7") (pinfunction "SW2_M7") (pintype "bidirectional"))
      (node (ref "U1") (pin "M8") (pinfunction "SW2_M8") (pintype "bidirectional"))
      (node (ref "U1") (pin "M9") (pinfunction "SW2_M9") (pintype "bidirectional"))
    )
    (net (code "37") (name "Net-(L2-Pad2)") (class "Default")
      (node (ref "L2") (pin "2") (pinfunction "2_2") (pintype "bidirectional"))
      (node (ref "U1") (pin "SW1@J1") (pinfunction "SW1_SW1@J1") (pintype "bidirectional"))
      (node (ref "U1") (pin "SW1@J2") (pinfunction "SW1_SW1@J2") (pintype "bidirectional"))
      (node (ref "U1") (pin "SW1@J3") (pinfunction "SW1_SW1@J3") (pintype "bidirectional"))
      (node (ref "U1") (pin "SW1@J4") (pinfunction "SW1_SW1@J4") (pintype "bidirectional"))
      (node (ref "U1") (pin "SW1@K1") (pinfunction "SW1_SW1@K1") (pintype "bidirectional"))
      (node (ref "U1") (pin "SW1@K2") (pinfunction "SW1_SW1@K2") (pintype "bidirectional"))
      (node (ref "U1") (pin "SW1@K3") (pinfunction "SW1_SW1@K3") (pintype "bidirectional"))
      (node (ref "U1") (pin "SW1@K4") (pinfunction "SW1_SW1@K4") (pintype "bidirectional"))
      (node (ref "U1") (pin "SW1@L1") (pinfunction "SW1_SW1@L1") (pintype "bidirectional"))
      (node (ref "U1") (pin "SW1@L2") (pinfunction "SW1_SW1@L2") (pintype "bidirectional"))
      (node (ref "U1") (pin "SW1@L3") (pinfunction "SW1_SW1@L3") (pintype "bidirectional"))
      (node (ref "U1") (pin "SW1@L4") (pinfunction "SW1_SW1@L4") (pintype "bidirectional"))
      (node (ref "U1") (pin "SW1@M1") (pinfunction "SW1_SW1@M1") (pintype "bidirectional"))
      (node (ref "U1") (pin "SW1@M2") (pinfunction "SW1_SW1@M2") (pintype "bidirectional"))
      (node (ref "U1") (pin "SW1@M3") (pinfunction "SW1_SW1@M3") (pintype "bidirectional"))
      (node (ref "U1") (pin "SW1@M4") (pinfunction "SW1_SW1@M4") (pintype "bidirectional"))
    )
    (net (code "38") (name "Net-(OK1-A1)") (class "Default")
      (node (ref "OK1") (pin "1") (pinfunction "A1_1") (pintype "bidirectional"))
      (node (ref "R5") (pin "2") (pinfunction "2_2") (pintype "passive"))
    )
    (net (code "39") (name "Net-(U1-PLLFLTR)") (class "Default")
      (node (ref "R1") (pin "2") (pinfunction "2_2") (pintype "passive"))
      (node (ref "R2") (pin "1") (pinfunction "1_1") (pintype "passive"))
      (node (ref "U1") (pin "B8") (pinfunction "PLLFLTR_B8") (pintype "bidirectional"))
    )
    (net (code "40") (name "Net-(U1-V_FB)") (class "Default")
      (node (ref "R4") (pin "2") (pinfunction "2_2") (pintype "passive"))
      (node (ref "U1") (pin "B6") (pinfunction "V_FB_B6") (pintype "bidirectional"))
    )
    (net (code "41") (name "OK1E1") (class "Default")
      (node (ref "OK2") (pin "15") (pinfunction "E1_15") (pintype "bidirectional"))
      (node (ref "R23") (pin "2") (pinfunction "2_2") (pintype "passive"))
      (node (ref "U3") (pin "3") (pinfunction "INPUT1_3") (pintype "bidirectional"))
    )
    (net (code "42") (name "OK1E2") (class "Default")
      (node (ref "OK2") (pin "13") (pinfunction "E2_13") (pintype "bidirectional"))
      (node (ref "R25") (pin "2") (pinfunction "2_2") (pintype "passive"))
      (node (ref "U3") (pin "5") (pinfunction "INPUT2_5") (pintype "bidirectional"))
    )
    (net (code "43") (name "OK1E3") (class "Default")
      (node (ref "OK2") (pin "11") (pinfunction "E3_11") (pintype "bidirectional"))
      (node (ref "R27") (pin "2") (pinfunction "2_2") (pintype "passive"))
      (node (ref "U3") (pin "7") (pinfunction "INPUT3_7") (pintype "bidirectional"))
    )
    (net (code "44") (name "OK1E4") (class "Default")
      (node (ref "OK2") (pin "9") (pinfunction "E4_9") (pintype "bidirectional"))
      (node (ref "R29") (pin "2") (pinfunction "2_2") (pintype "passive"))
      (node (ref "U3") (pin "9") (pinfunction "INPUT4_9") (pintype "bidirectional"))
    )
    (net (code "45") (name "OK2E1") (class "Default")
      (node (ref "OK3") (pin "15") (pinfunction "E1_15") (pintype "bidirectional"))
      (node (ref "R24") (pin "2") (pinfunction "2_2") (pintype "passive"))
      (node (ref "U4") (pin "3") (pinfunction "INPUT1_3") (pintype "bidirectional"))
    )
    (net (code "46") (name "OK2E2") (class "Default")
      (node (ref "OK3") (pin "13") (pinfunction "E2_13") (pintype "bidirectional"))
      (node (ref "R26") (pin "2") (pinfunction "2_2") (pintype "passive"))
      (node (ref "U4") (pin "5") (pinfunction "INPUT2_5") (pintype "bidirectional"))
    )
    (net (code "47") (name "OK2E3") (class "Default")
      (node (ref "OK3") (pin "11") (pinfunction "E3_11") (pintype "bidirectional"))
      (node (ref "R28") (pin "2") (pinfunction "2_2") (pintype "passive"))
      (node (ref "U4") (pin "7") (pinfunction "INPUT3_7") (pintype "bidirectional"))
    )
    (net (code "48") (name "OK2E4") (class "Default")
      (node (ref "OK3") (pin "9") (pinfunction "E4_9") (pintype "bidirectional"))
      (node (ref "R30") (pin "2") (pinfunction "2_2") (pintype "passive"))
      (node (ref "U4") (pin "9") (pinfunction "INPUT4_9") (pintype "bidirectional"))
    )
    (net (code "49") (name "P3") (class "Default")
      (node (ref "R5") (pin "1") (pinfunction "1_1") (pintype "passive"))
      (node (ref "SJ2") (pin "2") (pinfunction "2_2") (pintype "passive"))
      (node (ref "U2") (pin "17") (pinfunction "VCC3V_17") (pintype "bidirectional"))
      (node (ref "U2") (pin "47") (pinfunction "VCC3V_47") (pintype "bidirectional"))
    )
    (net (code "50") (name "P3_SW") (class "Default")
      (node (ref "J2") (pin "4") (pinfunction "4_4") (pintype "bidirectional"))
      (node (ref "J3") (pin "2") (pinfunction "2_2") (pintype "bidirectional"))
      (node (ref "SJ2") (pin "1") (pinfunction "1_1") (pintype "passive"))
    )
    (net (code "51") (name "P18_SW1") (class "Default")
      (node (ref "OK2") (pin "1") (pinfunction "A1_1") (pintype "bidirectional"))
      (node (ref "R7") (pin "1") (pinfunction "1_1") (pintype "passive"))
    )
    (net (code "52") (name "P18_SW2") (class "Default")
      (node (ref "OK2") (pin "5") (pinfunction "A3_5") (pintype "bidirectional"))
      (node (ref "R8") (pin "1") (pinfunction "1_1") (pintype "passive"))
    )
    (net (code "53") (name "P18_SW3") (class "Default")
      (node (ref "OK3") (pin "1") (pinfunction "A1_1") (pintype "bidirectional"))
      (node (ref "R9") (pin "1") (pinfunction "1_1") (pintype "passive"))
    )
    (net (code "54") (name "P18_SW4") (class "Default")
      (node (ref "OK3") (pin "5") (pinfunction "A3_5") (pintype "bidirectional"))
      (node (ref "R10") (pin "1") (pinfunction "1_1") (pintype "passive"))
    )
    (net (code "55") (name "P18_SW5") (class "Default")
      (node (ref "OK2") (pin "3") (pinfunction "A2_3") (pintype "bidirectional"))
      (node (ref "R11") (pin "1") (pinfunction "1_1") (pintype "passive"))
    )
    (net (code "56") (name "P18_SW6") (class "Default")
      (node (ref "OK2") (pin "7") (pinfunction "A4_7") (pintype "bidirectional"))
      (node (ref "R12") (pin "1") (pinfunction "1_1") (pintype "passive"))
    )
    (net (code "57") (name "P18_SW7") (class "Default")
      (node (ref "OK3") (pin "3") (pinfunction "A2_3") (pintype "bidirectional"))
      (node (ref "R13") (pin "1") (pinfunction "1_1") (pintype "passive"))
    )
    (net (code "58") (name "P18_SW8") (class "Default")
      (node (ref "OK3") (pin "7") (pinfunction "A4_7") (pintype "bidirectional"))
      (node (ref "R14") (pin "1") (pinfunction "1_1") (pintype "passive"))
    )
    (net (code "59") (name "PBATT_SW") (class "Default")
      (node (ref "J2") (pin "5") (pinfunction "5_5") (pintype "bidirectional"))
      (node (ref "SJ1") (pin "1") (pinfunction "1_1") (pintype "passive"))
    )
    (net (code "60") (name "PGND") (class "Default")
      (node (ref "C3") (pin "2") (pinfunction "2_2") (pintype "passive"))
      (node (ref "C4") (pin "2") (pinfunction "2_2") (pintype "passive"))
      (node (ref "C5") (pin "K1") (pinfunction "K_K1") (pintype "passive"))
      (node (ref "J3") (pin "1") (pinfunction "1_1") (pintype "bidirectional"))
      (node (ref "J3") (pin "6") (pinfunction "6_6") (pintype "bidirectional"))
      (node (ref "J4") (pin "1") (pinfunction "1_1") (pintype "bidirectional"))
      (node (ref "J4") (pin "4") (pinfunction "4_4") (pintype "bidirectional"))
      (node (ref "J5") (pin "1") (pinfunction "1_1") (pintype "bidirectional"))
      (node (ref "J5") (pin "4") (pinfunction "4_4") (pintype "bidirectional"))
      (node (ref "OK1") (pin "15") (pinfunction "E1_15") (pintype "bidirectional"))
      (node (ref "R23") (pin "1") (pinfunction "1_1") (pintype "passive"))
      (node (ref "R24") (pin "1") (pinfunction "1_1") (pintype "passive"))
      (node (ref "R25") (pin "1") (pinfunction "1_1") (pintype "passive"))
      (node (ref "R26") (pin "1") (pinfunction "1_1") (pintype "passive"))
      (node (ref "R27") (pin "1") (pinfunction "1_1") (pintype "passive"))
      (node (ref "R28") (pin "1") (pinfunction "1_1") (pintype "passive"))
      (node (ref "R29") (pin "1") (pinfunction "1_1") (pintype "passive"))
      (node (ref "R3") (pin "2") (pinfunction "2_2") (pintype "passive"))
      (node (ref "R30") (pin "1") (pinfunction "1_1") (pintype "passive"))
      (node (ref "R36") (pin "2") (pinfunction "2_2") (pintype "passive"))
      (node (ref "R4") (pin "1") (pinfunction "1_1") (pintype "passive"))
      (node (ref "SJ3") (pin "1") (pinfunction "1_1") (pintype "passive"))
      (node (ref "U1") (pin "A1") (pinfunction "PGND_A1") (pintype "bidirectional"))
      (node (ref "U1") (pin "A11") (pinfunction "PGND_A11") (pintype "bidirectional"))
      (node (ref "U1") (pin "A12") (pinfunction "PGND_A12") (pintype "bidirectional"))
      (node (ref "U1") (pin "A2") (pinfunction "PGND_A2") (pintype "bidirectional"))
      (node (ref "U1") (pin "A3") (pinfunction "PGND_A3") (pintype "bidirectional"))
      (node (ref "U1") (pin "A5") (pinfunction "SENSE-_A5") (pintype "bidirectional"))
      (node (ref "U1") (pin "B1") (pinfunction "PGND_B1") (pintype "bidirectional"))
      (node (ref "U1") (pin "B10") (pinfunction "PGND_B10") (pintype "bidirectional"))
      (node (ref "U1") (pin "B11") (pinfunction "PGND_B11") (pintype "bidirectional"))
      (node (ref "U1") (pin "B12") (pinfunction "PGND_B12") (pintype "bidirectional"))
      (node (ref "U1") (pin "B2") (pinfunction "PGND_B2") (pintype "bidirectional"))
      (node (ref "U1") (pin "B3") (pinfunction "PGND_B3") (pintype "bidirectional"))
      (node (ref "U1") (pin "B4") (pinfunction "PGND_B4") (pintype "bidirectional"))
      (node (ref "U1") (pin "C1") (pinfunction "PGND_C1") (pintype "bidirectional"))
      (node (ref "U1") (pin "C10") (pinfunction "PGND_C10") (pintype "bidirectional"))
      (node (ref "U1") (pin "C11") (pinfunction "PGND_C11") (pintype "bidirectional"))
      (node (ref "U1") (pin "C12") (pinfunction "PGND_C12") (pintype "bidirectional"))
      (node (ref "U1") (pin "C2") (pinfunction "PGND_C2") (pintype "bidirectional"))
      (node (ref "U1") (pin "C3") (pinfunction "PGND_C3") (pintype "bidirectional"))
      (node (ref "U1") (pin "C4") (pinfunction "PGND_C4") (pintype "bidirectional"))
      (node (ref "U1") (pin "C5") (pinfunction "PGND_C5") (pintype "bidirectional"))
      (node (ref "U1") (pin "C6") (pinfunction "PGND_C6") (pintype "bidirectional"))
      (node (ref "U1") (pin "C7") (pinfunction "PGND_C7") (pintype "bidirectional"))
      (node (ref "U1") (pin "C8") (pinfunction "PGND_C8") (pintype "bidirectional"))
      (node (ref "U1") (pin "C9") (pinfunction "PGND_C9") (pintype "bidirectional"))
      (node (ref "U1") (pin "D1") (pinfunction "PGND_D1") (pintype "bidirectional"))
      (node (ref "U1") (pin "D10") (pinfunction "PGND_D10") (pintype "bidirectional"))
      (node (ref "U1") (pin "D11") (pinfunction "PGND_D11") (pintype "bidirectional"))
      (node (ref "U1") (pin "D12") (pinfunction "PGND_D12") (pintype "bidirectional"))
      (node (ref "U1") (pin "D2") (pinfunction "PGND_D2") (pintype "bidirectional"))
      (node (ref "U1") (pin "D3") (pinfunction "PGND_D3") (pintype "bidirectional"))
      (node (ref "U1") (pin "D4") (pinfunction "PGND_D4") (pintype "bidirectional"))
      (node (ref "U1") (pin "D5") (pinfunction "PGND_D5") (pintype "bidirectional"))
      (node (ref "U1") (pin "D6") (pinfunction "PGND_D6") (pintype "bidirectional"))
      (node (ref "U1") (pin "D7") (pinfunction "PGND_D7") (pintype "bidirectional"))
      (node (ref "U1") (pin "D8") (pinfunction "PGND_D8") (pintype "bidirectional"))
      (node (ref "U1") (pin "D9") (pinfunction "PGND_D9") (pintype "bidirectional"))
      (node (ref "U1") (pin "E10") (pinfunction "PGND_E10") (pintype "bidirectional"))
      (node (ref "U1") (pin "E11") (pinfunction "PGND_E11") (pintype "bidirectional"))
      (node (ref "U1") (pin "E12") (pinfunction "PGND_E12") (pintype "bidirectional"))
      (node (ref "U1") (pin "E3") (pinfunction "PGND_E3") (pintype "bidirectional"))
      (node (ref "U1") (pin "E4") (pinfunction "PGND_E4") (pintype "bidirectional"))
      (node (ref "U1") (pin "E5") (pinfunction "PGND_E5") (pintype "bidirectional"))
      (node (ref "U1") (pin "E6") (pinfunction "PGND_E6") (pintype "bidirectional"))
      (node (ref "U1") (pin "E7") (pinfunction "PGND_E7") (pintype "bidirectional"))
      (node (ref "U1") (pin "E8") (pinfunction "PGND_E8") (pintype "bidirectional"))
      (node (ref "U1") (pin "E9") (pinfunction "PGND_E9") (pintype "bidirectional"))
      (node (ref "U3") (pin "1") (pinfunction "GND_1") (pintype "bidirectional"))
      (node (ref "U3") (pin "10") (pinfunction "GND_10") (pintype "bidirectional"))
      (node (ref "U4") (pin "1") (pinfunction "GND_1") (pintype "bidirectional"))
      (node (ref "U4") (pin "10") (pinfunction "GND_10") (pintype "bidirectional"))
    )
    (net (code "61") (name "PGOOD_PMA") (class "Default")
      (node (ref "J3") (pin "4") (pinfunction "4_4") (pintype "bidirectional"))
      (node (ref "U1") (pin "B5") (pinfunction "PGOOD_B5") (pintype "bidirectional"))
    )
    (net (code "62") (name "RSENSE") (class "Default")
      (node (ref "R3") (pin "1") (pinfunction "1_1") (pintype "passive"))
      (node (ref "U1") (pin "A4") (pinfunction "SENSE+_A4") (pintype "bidirectional"))
      (node (ref "U1") (pin "F10") (pinfunction "R_SENSE_F10") (pintype "bidirectional"))
      (node (ref "U1") (pin "F11") (pinfunction "R_SENSE_F11") (pintype "bidirectional"))
      (node (ref "U1") (pin "F12") (pinfunction "R_SENSE_F12") (pintype "bidirectional"))
      (node (ref "U1") (pin "G10") (pinfunction "R_SENSE_G10") (pintype "bidirectional"))
      (node (ref "U1") (pin "G11") (pinfunction "R_SENSE_G11") (pintype "bidirectional"))
      (node (ref "U1") (pin "G12") (pinfunction "R_SENSE_G12") (pintype "bidirectional"))
      (node (ref "U1") (pin "G5") (pinfunction "R_SENSE_G5") (pintype "bidirectional"))
      (node (ref "U1") (pin "G6") (pinfunction "R_SENSE_G6") (pintype "bidirectional"))
      (node (ref "U1") (pin "G7") (pinfunction "R_SENSE_G7") (pintype "bidirectional"))
      (node (ref "U1") (pin "G8") (pinfunction "R_SENSE_G8") (pintype "bidirectional"))
      (node (ref "U1") (pin "G9") (pinfunction "R_SENSE_G9") (pintype "bidirectional"))
      (node (ref "U1") (pin "H10") (pinfunction "R_SENSE_H10") (pintype "bidirectional"))
      (node (ref "U1") (pin "H11") (pinfunction "R_SENSE_H11") (pintype "bidirectional"))
      (node (ref "U1") (pin "H12") (pinfunction "R_SENSE_H12") (pintype "bidirectional"))
      (node (ref "U1") (pin "H5") (pinfunction "R_SENSE_H5") (pintype "bidirectional"))
      (node (ref "U1") (pin "H6") (pinfunction "R_SENSE_H6") (pintype "bidirectional"))
      (node (ref "U1") (pin "H7") (pinfunction "R_SENSE_H7") (pintype "bidirectional"))
      (node (ref "U1") (pin "H8") (pinfunction "R_SENSE_H8") (pintype "bidirectional"))
      (node (ref "U1") (pin "H9") (pinfunction "R_SENSE_H9") (pintype "bidirectional"))
      (node (ref "U1") (pin "J5") (pinfunction "R_SENSE_J5") (pintype "bidirectional"))
      (node (ref "U1") (pin "J6") (pinfunction "R_SENSE_J6") (pintype "bidirectional"))
      (node (ref "U1") (pin "J7") (pinfunction "R_SENSE_J7") (pintype "bidirectional"))
      (node (ref "U1") (pin "K5") (pinfunction "R_SENSE_K5") (pintype "bidirectional"))
      (node (ref "U1") (pin "K6") (pinfunction "R_SENSE_K6") (pintype "bidirectional"))
      (node (ref "U1") (pin "L5") (pinfunction "R_SENSE_L5") (pintype "bidirectional"))
      (node (ref "U1") (pin "L6") (pinfunction "R_SENSE_L6") (pintype "bidirectional"))
      (node (ref "U1") (pin "M5") (pinfunction "R_SENSE_M5") (pintype "bidirectional"))
      (node (ref "U1") (pin "M6") (pinfunction "R_SENSE_M6") (pintype "bidirectional"))
    )
    (net (code "63") (name "SGND") (class "Default")
      (node (ref "R2") (pin "2") (pinfunction "2_2") (pintype "passive"))
      (node (ref "SJ3") (pin "2") (pinfunction "2_2") (pintype "passive"))
      (node (ref "SJ4") (pin "2") (pinfunction "2_2") (pintype "passive"))
      (node (ref "U1") (pin "A7") (pinfunction "SGND_A7") (pintype "bidirectional"))
    )
    (net (code "64") (name "SW_P18H1") (class "Default")
      (node (ref "R11") (pin "2") (pinfunction "2_2") (pintype "passive"))
      (node (ref "U2") (pin "35") (pinfunction "SDHC_DAT0_35") (pintype "bidirectional"))
    )
    (net (code "65") (name "SW_P18H2") (class "Default")
      (node (ref "R12") (pin "2") (pinfunction "2_2") (pintype "passive"))
      (node (ref "U2") (pin "34") (pinfunction "UART1_TX_34") (pintype "bidirectional"))
    )
    (net (code "66") (name "SW_P18H3") (class "Default")
      (node (ref "R13") (pin "2") (pinfunction "2_2") (pintype "passive"))
      (node (ref "U2") (pin "33") (pinfunction "SDHC_CMD_33") (pintype "bidirectional"))
    )
    (net (code "67") (name "SW_P18H4") (class "Default")
      (node (ref "R14") (pin "2") (pinfunction "2_2") (pintype "passive"))
      (node (ref "U2") (pin "32") (pinfunction "UART1_RX_32") (pintype "bidirectional"))
    )
    (net (code "68") (name "SW_P18L1") (class "Default")
      (node (ref "R7") (pin "2") (pinfunction "2_2") (pintype "passive"))
      (node (ref "U2") (pin "39") (pinfunction "SDHC_DAT2_39") (pintype "bidirectional"))
    )
    (net (code "69") (name "SW_P18L2") (class "Default")
      (node (ref "R8") (pin "2") (pinfunction "2_2") (pintype "passive"))
      (node (ref "U2") (pin "38") (pinfunction "UART1_CTS_38") (pintype "bidirectional"))
    )
    (net (code "70") (name "SW_P18L3") (class "Default")
      (node (ref "R9") (pin "2") (pinfunction "2_2") (pintype "passive"))
      (node (ref "U2") (pin "37") (pinfunction "SDHC_DAT1_37") (pintype "bidirectional"))
    )
    (net (code "71") (name "SW_P18L4") (class "Default")
      (node (ref "R10") (pin "2") (pinfunction "2_2") (pintype "passive"))
      (node (ref "U2") (pin "36") (pinfunction "UART1_RTS_36") (pintype "bidirectional"))
    )
    (net (code "72") (name "SW_RUNPMA") (class "Default")
      (node (ref "U1") (pin "A8") (pinfunction "RUN_A8") (pintype "bidirectional"))
      (node (ref "U2") (pin "23") (pinfunction "T2IN_23") (pintype "bidirectional"))
    )
    (net (code "73") (name "SW_TP1") (class "Default")
      (node (ref "J3") (pin "7") (pinfunction "7_7") (pintype "bidirectional"))
      (node (ref "OK1") (pin "2") (pinfunction "K1_2") (pintype "bidirectional"))
      (node (ref "U2") (pin "31") (pinfunction "SDHC_CLK_31") (pintype "bidirectional"))
    )
    (net (code "74") (name "TP1_OUT") (class "Default")
      (node (ref "J3") (pin "8") (pinfunction "8_8") (pintype "bidirectional"))
      (node (ref "J4") (pin "3") (pinfunction "3_3") (pintype "bidirectional"))
      (node (ref "J4") (pin "6") (pinfunction "6_6") (pintype "bidirectional"))
      (node (ref "J5") (pin "3") (pinfunction "3_3") (pintype "bidirectional"))
      (node (ref "J5") (pin "6") (pinfunction "6_6") (pintype "bidirectional"))
      (node (ref "OK1") (pin "16") (pinfunction "C1_16") (pintype "bidirectional"))
      (node (ref "R35") (pin "2") (pinfunction "2_2") (pintype "passive"))
      (node (ref "R36") (pin "1") (pinfunction "1_1") (pintype "passive"))
    )
    (net (code "75") (name "UART0_RX") (class "Default")
      (node (ref "J2") (pin "6") (pinfunction "6_6") (pintype "bidirectional"))
      (node (ref "J6") (pin "3") (pinfunction "3_3") (pintype "bidirectional"))
      (node (ref "U2") (pin "24") (pinfunction "UART0_RX_24") (pintype "bidirectional"))
    )
    (net (code "76") (name "UART0_TX") (class "Default")
      (node (ref "J2") (pin "3") (pinfunction "3_3") (pintype "bidirectional"))
      (node (ref "J6") (pin "2") (pinfunction "2_2") (pintype "bidirectional"))
      (node (ref "U2") (pin "26") (pinfunction "UART0_TX_26") (pintype "bidirectional"))
    )
    (net (code "77") (name "VBATT_IN") (class "Default")
      (node (ref "C1") (pin "A1") (pinfunction "A_A1") (pintype "passive"))
      (node (ref "J3") (pin "3") (pinfunction "3_3") (pintype "bidirectional"))
      (node (ref "L1") (pin "1") (pinfunction "1_1") (pintype "bidirectional"))
      (node (ref "SJ1") (pin "2") (pinfunction "2_2") (pintype "passive"))
    )
    (net (code "78") (name "VIN") (class "Default")
      (node (ref "C2") (pin "1") (pinfunction "1_1") (pintype "passive"))
      (node (ref "L1") (pin "2") (pinfunction "2_2") (pintype "bidirectional"))
      (node (ref "U1") (pin "J10") (pinfunction "V_IN_J10") (pintype "bidirectional"))
      (node (ref "U1") (pin "J11") (pinfunction "V_IN_J11") (pintype "bidirectional"))
      (node (ref "U1") (pin "J12") (pinfunction "V_IN_J12") (pintype "bidirectional"))
      (node (ref "U1") (pin "K10") (pinfunction "V_IN_K10") (pintype "bidirectional"))
      (node (ref "U1") (pin "K11") (pinfunction "V_IN_K11") (pintype "bidirectional"))
      (node (ref "U1") (pin "K12") (pinfunction "V_IN_K12") (pintype "bidirectional"))
      (node (ref "U1") (pin "L10") (pinfunction "V_IN_L10") (pintype "bidirectional"))
      (node (ref "U1") (pin "L11") (pinfunction "V_IN_L11") (pintype "bidirectional"))
      (node (ref "U1") (pin "L12") (pinfunction "V_IN_L12") (pintype "bidirectional"))
      (node (ref "U1") (pin "M10") (pinfunction "V_IN_M10") (pintype "bidirectional"))
      (node (ref "U1") (pin "M11") (pinfunction "V_IN_M11") (pintype "bidirectional"))
      (node (ref "U1") (pin "M12") (pinfunction "V_IN_M12") (pintype "bidirectional"))
    )
    (net (code "79") (name "VOUT") (class "Default")
      (node (ref "C3") (pin "1") (pinfunction "1_1") (pintype "passive"))
      (node (ref "C4") (pin "1") (pinfunction "1_1") (pintype "passive"))
      (node (ref "L3") (pin "1") (pinfunction "1_1") (pintype "bidirectional"))
      (node (ref "U1") (pin "E1") (pinfunction "V_OUT_E1") (pintype "bidirectional"))
      (node (ref "U1") (pin "E2") (pinfunction "V_OUT_E2") (pintype "bidirectional"))
      (node (ref "U1") (pin "F1") (pinfunction "V_OUT_F1") (pintype "bidirectional"))
      (node (ref "U1") (pin "F2") (pinfunction "V_OUT_F2") (pintype "bidirectional"))
      (node (ref "U1") (pin "F3") (pinfunction "V_OUT_F3") (pintype "bidirectional"))
      (node (ref "U1") (pin "F4") (pinfunction "V_OUT_F4") (pintype "bidirectional"))
      (node (ref "U1") (pin "G1") (pinfunction "V_OUT_G1") (pintype "bidirectional"))
      (node (ref "U1") (pin "G2") (pinfunction "V_OUT_G2") (pintype "bidirectional"))
      (node (ref "U1") (pin "G3") (pinfunction "V_OUT_G3") (pintype "bidirectional"))
      (node (ref "U1") (pin "G4") (pinfunction "V_OUT_G4") (pintype "bidirectional"))
      (node (ref "U1") (pin "H2") (pinfunction "V_OUT_H2") (pintype "bidirectional"))
      (node (ref "U1") (pin "H3") (pinfunction "V_OUT_H3") (pintype "bidirectional"))
      (node (ref "U1") (pin "H4") (pinfunction "V_OUT_H4") (pintype "bidirectional"))
      (node (ref "U1") (pin "VOUT") (pinfunction "V_OUT_VOUT") (pintype "bidirectional"))
    )
    (net (code "80") (name "VOUTA") (class "Default")
      (node (ref "C5") (pin "A1") (pinfunction "A_A1") (pintype "passive"))
      (node (ref "J3") (pin "5") (pinfunction "5_5") (pintype "bidirectional"))
      (node (ref "L3") (pin "2") (pinfunction "2_2") (pintype "bidirectional"))
      (node (ref "Q1") (pin "D") (pinfunction "D_D") (pintype "bidirectional"))
      (node (ref "Q3") (pin "D") (pinfunction "D_D") (pintype "bidirectional"))
      (node (ref "Q5") (pin "D") (pinfunction "D_D") (pintype "bidirectional"))
      (node (ref "Q7") (pin "D") (pinfunction "D_D") (pintype "bidirectional"))
      (node (ref "R15") (pin "1") (pinfunction "1_1") (pintype "passive"))
      (node (ref "R16") (pin "1") (pinfunction "1_1") (pintype "passive"))
      (node (ref "R17") (pin "1") (pinfunction "1_1") (pintype "passive"))
      (node (ref "R18") (pin "1") (pinfunction "1_1") (pintype "passive"))
      (node (ref "R19") (pin "1") (pinfunction "1_1") (pintype "passive"))
      (node (ref "R20") (pin "1") (pinfunction "1_1") (pintype "passive"))
      (node (ref "R21") (pin "1") (pinfunction "1_1") (pintype "passive"))
      (node (ref "R22") (pin "1") (pinfunction "1_1") (pintype "passive"))
      (node (ref "R31") (pin "2") (pinfunction "2_2") (pintype "passive"))
      (node (ref "R32") (pin "2") (pinfunction "2_2") (pintype "passive"))
      (node (ref "R33") (pin "2") (pinfunction "2_2") (pintype "passive"))
      (node (ref "R34") (pin "2") (pinfunction "2_2") (pintype "passive"))
      (node (ref "R35") (pin "1") (pinfunction "1_1") (pintype "passive"))
      (node (ref "U3") (pin "11") (pinfunction "V+_11") (pintype "bidirectional"))
      (node (ref "U3") (pin "13") (pinfunction "SENSE4_13") (pintype "bidirectional"))
      (node (ref "U3") (pin "15") (pinfunction "SENSE3_15") (pintype "bidirectional"))
      (node (ref "U3") (pin "17") (pinfunction "SENSE2_17") (pintype "bidirectional"))
      (node (ref "U3") (pin "19") (pinfunction "SENSE1_19") (pintype "bidirectional"))
      (node (ref "U3") (pin "20") (pinfunction "V+_20") (pintype "bidirectional"))
      (node (ref "U4") (pin "11") (pinfunction "V+_11") (pintype "bidirectional"))
      (node (ref "U4") (pin "13") (pinfunction "SENSE4_13") (pintype "bidirectional"))
      (node (ref "U4") (pin "15") (pinfunction "SENSE3_15") (pintype "bidirectional"))
      (node (ref "U4") (pin "17") (pinfunction "SENSE2_17") (pintype "bidirectional"))
      (node (ref "U4") (pin "19") (pinfunction "SENSE1_19") (pintype "bidirectional"))
      (node (ref "U4") (pin "20") (pinfunction "V+_20") (pintype "bidirectional"))
    )
    (net (code "81") (name "unconnected-(J1-+5V_SW-Pad33)") (class "Default")
      (node (ref "J1") (pin "33") (pinfunction "+5V_SW_33") (pintype "bidirectional"))
    )
    (net (code "82") (name "unconnected-(J1-+5V_SYS-Pad77)") (class "Default")
      (node (ref "J1") (pin "77") (pinfunction "+5V_SYS_77") (pintype "bidirectional"))
    )
    (net (code "83") (name "unconnected-(J1-+5V_SYS-Pad78)") (class "Default")
      (node (ref "J1") (pin "78") (pinfunction "+5V_SYS_78") (pintype "bidirectional"))
    )
    (net (code "84") (name "unconnected-(J1-+5V_USB-Pad32)") (class "Default")
      (node (ref "J1") (pin "32") (pinfunction "+5V_USB_32") (pintype "bidirectional"))
    )
    (net (code "85") (name "unconnected-(J1--CTS_MHX-Pad35)") (class "Default")
      (node (ref "J1") (pin "35") (pinfunction "-CTS_MHX_35") (pintype "bidirectional"))
    )
    (net (code "86") (name "unconnected-(J1--DSR_MHX-Pad37)") (class "Default")
      (node (ref "J1") (pin "37") (pinfunction "-DSR_MHX_37") (pintype "bidirectional"))
    )
    (net (code "87") (name "unconnected-(J1--DTR_MHX-Pad38)") (class "Default")
      (node (ref "J1") (pin "38") (pinfunction "-DTR_MHX_38") (pintype "bidirectional"))
    )
    (net (code "88") (name "unconnected-(J1--FAULT-Pad25)") (class "Default")
      (node (ref "J1") (pin "25") (pinfunction "-FAULT_25") (pintype "bidirectional"))
    )
    (net (code "89") (name "unconnected-(J1--RESET-Pad29)") (class "Default")
      (node (ref "J1") (pin "29") (pinfunction "-RESET_29") (pintype "bidirectional"))
    )
    (net (code "90") (name "unconnected-(J1--RST_MHX-Pad34)") (class "Default")
      (node (ref "J1") (pin "34") (pinfunction "-RST_MHX_34") (pintype "bidirectional"))
    )
    (net (code "91") (name "unconnected-(J1--RTS_MHX-Pad36)") (class "Default")
      (node (ref "J1") (pin "36") (pinfunction "-RTS_MHX_36") (pintype "bidirectional"))
    )
    (net (code "92") (name "unconnected-(J1-OFF_VCC-Pad31)") (class "Default")
      (node (ref "J1") (pin "31") (pinfunction "OFF_VCC_31") (pintype "bidirectional"))
    )
    (net (code "93") (name "unconnected-(J1-P1.0-Pad68)") (class "Default")
      (node (ref "J1") (pin "68") (pinfunction "P1.0_68") (pintype "bidirectional"))
    )
    (net (code "94") (name "unconnected-(J1-P1.1-Pad67)") (class "Default")
      (node (ref "J1") (pin "67") (pinfunction "P1.1_67") (pintype "bidirectional"))
    )
    (net (code "95") (name "unconnected-(J1-P1.2-Pad66)") (class "Default")
      (node (ref "J1") (pin "66") (pinfunction "P1.2_66") (pintype "bidirectional"))
    )
    (net (code "96") (name "unconnected-(J1-P1.3-Pad65)") (class "Default")
      (node (ref "J1") (pin "65") (pinfunction "P1.3_65") (pintype "bidirectional"))
    )
    (net (code "97") (name "unconnected-(J1-P1.4-Pad64)") (class "Default")
      (node (ref "J1") (pin "64") (pinfunction "P1.4_64") (pintype "bidirectional"))
    )
    (net (code "98") (name "unconnected-(J1-P1.5-Pad63)") (class "Default")
      (node (ref "J1") (pin "63") (pinfunction "P1.5_63") (pintype "bidirectional"))
    )
    (net (code "99") (name "unconnected-(J1-P1.6-Pad62)") (class "Default")
      (node (ref "J1") (pin "62") (pinfunction "P1.6_62") (pintype "bidirectional"))
    )
    (net (code "100") (name "unconnected-(J1-P1.7-Pad61)") (class "Default")
      (node (ref "J1") (pin "61") (pinfunction "P1.7_61") (pintype "bidirectional"))
    )
    (net (code "101") (name "unconnected-(J1-P2.0-Pad76)") (class "Default")
      (node (ref "J1") (pin "76") (pinfunction "P2.0_76") (pintype "bidirectional"))
    )
    (net (code "102") (name "unconnected-(J1-P2.1-Pad75)") (class "Default")
      (node (ref "J1") (pin "75") (pinfunction "P2.1_75") (pintype "bidirectional"))
    )
    (net (code "103") (name "unconnected-(J1-P2.2-Pad74)") (class "Default")
      (node (ref "J1") (pin "74") (pinfunction "P2.2_74") (pintype "bidirectional"))
    )
    (net (code "104") (name "unconnected-(J1-P2.3-Pad73)") (class "Default")
      (node (ref "J1") (pin "73") (pinfunction "P2.3_73") (pintype "bidirectional"))
    )
    (net (code "105") (name "unconnected-(J1-P2.4-Pad72)") (class "Default")
      (node (ref "J1") (pin "72") (pinfunction "P2.4_72") (pintype "bidirectional"))
    )
    (net (code "106") (name "unconnected-(J1-P2.5-Pad71)") (class "Default")
      (node (ref "J1") (pin "71") (pinfunction "P2.5_71") (pintype "bidirectional"))
    )
    (net (code "107") (name "unconnected-(J1-P2.6-Pad70)") (class "Default")
      (node (ref "J1") (pin "70") (pinfunction "P2.6_70") (pintype "bidirectional"))
    )
    (net (code "108") (name "unconnected-(J1-P2.7-Pad69)") (class "Default")
      (node (ref "J1") (pin "69") (pinfunction "P2.7_69") (pintype "bidirectional"))
    )
    (net (code "109") (name "unconnected-(J1-P3.0-Pad24)") (class "Default")
      (node (ref "J1") (pin "24") (pinfunction "P3.0_24") (pintype "bidirectional"))
    )
    (net (code "110") (name "unconnected-(J1-P3.1-Pad23)") (class "Default")
      (node (ref "J1") (pin "23") (pinfunction "P3.1_23") (pintype "bidirectional"))
    )
    (net (code "111") (name "unconnected-(J1-P3.2-Pad22)") (class "Default")
      (node (ref "J1") (pin "22") (pinfunction "P3.2_22") (pintype "bidirectional"))
    )
    (net (code "112") (name "unconnected-(J1-P3.3-Pad21)") (class "Default")
      (node (ref "J1") (pin "21") (pinfunction "P3.3_21") (pintype "bidirectional"))
    )
    (net (code "113") (name "unconnected-(J1-P3.4-Pad20)") (class "Default")
      (node (ref "J1") (pin "20") (pinfunction "P3.4_20") (pintype "bidirectional"))
    )
    (net (code "114") (name "unconnected-(J1-P3.5-Pad19)") (class "Default")
      (node (ref "J1") (pin "19") (pinfunction "P3.5_19") (pintype "bidirectional"))
    )
    (net (code "115") (name "unconnected-(J1-P3.6-Pad18)") (class "Default")
      (node (ref "J1") (pin "18") (pinfunction "P3.6_18") (pintype "bidirectional"))
    )
    (net (code "116") (name "unconnected-(J1-P3.7-Pad17)") (class "Default")
      (node (ref "J1") (pin "17") (pinfunction "P3.7_17") (pintype "bidirectional"))
    )
    (net (code "117") (name "unconnected-(J1-P4.0-Pad16)") (class "Default")
      (node (ref "J1") (pin "16") (pinfunction "P4.0_16") (pintype "bidirectional"))
    )
    (net (code "118") (name "unconnected-(J1-P4.1-Pad15)") (class "Default")
      (node (ref "J1") (pin "15") (pinfunction "P4.1_15") (pintype "bidirectional"))
    )
    (net (code "119") (name "unconnected-(J1-P4.2-Pad14)") (class "Default")
      (node (ref "J1") (pin "14") (pinfunction "P4.2_14") (pintype "bidirectional"))
    )
    (net (code "120") (name "unconnected-(J1-P4.3-Pad13)") (class "Default")
      (node (ref "J1") (pin "13") (pinfunction "P4.3_13") (pintype "bidirectional"))
    )
    (net (code "121") (name "unconnected-(J1-P4.4-Pad12)") (class "Default")
      (node (ref "J1") (pin "12") (pinfunction "P4.4_12") (pintype "bidirectional"))
    )
    (net (code "122") (name "unconnected-(J1-P4.5-Pad11)") (class "Default")
      (node (ref "J1") (pin "11") (pinfunction "P4.5_11") (pintype "bidirectional"))
    )
    (net (code "123") (name "unconnected-(J1-P4.6-Pad10)") (class "Default")
      (node (ref "J1") (pin "10") (pinfunction "P4.6_10") (pintype "bidirectional"))
    )
    (net (code "124") (name "unconnected-(J1-P4.7-Pad9)") (class "Default")
      (node (ref "J1") (pin "9") (pinfunction "P4.7_9") (pintype "bidirectional"))
    )
    (net (code "125") (name "unconnected-(J1-P5.0-Pad8)") (class "Default")
      (node (ref "J1") (pin "8") (pinfunction "P5.0_8") (pintype "bidirectional"))
    )
    (net (code "126") (name "unconnected-(J1-P5.1-Pad7)") (class "Default")
      (node (ref "J1") (pin "7") (pinfunction "P5.1_7") (pintype "bidirectional"))
    )
    (net (code "127") (name "unconnected-(J1-P5.2-Pad6)") (class "Default")
      (node (ref "J1") (pin "6") (pinfunction "P5.2_6") (pintype "bidirectional"))
    )
    (net (code "128") (name "unconnected-(J1-P5.3-Pad5)") (class "Default")
      (node (ref "J1") (pin "5") (pinfunction "P5.3_5") (pintype "bidirectional"))
    )
    (net (code "129") (name "unconnected-(J1-P5.4-Pad4)") (class "Default")
      (node (ref "J1") (pin "4") (pinfunction "P5.4_4") (pintype "bidirectional"))
    )
    (net (code "130") (name "unconnected-(J1-P5.5-Pad3)") (class "Default")
      (node (ref "J1") (pin "3") (pinfunction "P5.5_3") (pintype "bidirectional"))
    )
    (net (code "131") (name "unconnected-(J1-P5.6-Pad2)") (class "Default")
      (node (ref "J1") (pin "2") (pinfunction "P5.6_2") (pintype "bidirectional"))
    )
    (net (code "132") (name "unconnected-(J1-P5.7-Pad1)") (class "Default")
      (node (ref "J1") (pin "1") (pinfunction "P5.7_1") (pintype "bidirectional"))
    )
    (net (code "133") (name "unconnected-(J1-P6.0-Pad60)") (class "Default")
      (node (ref "J1") (pin "60") (pinfunction "P6.0_60") (pintype "bidirectional"))
    )
    (net (code "134") (name "unconnected-(J1-P6.1-Pad59)") (class "Default")
      (node (ref "J1") (pin "59") (pinfunction "P6.1_59") (pintype "bidirectional"))
    )
    (net (code "135") (name "unconnected-(J1-P6.2-Pad58)") (class "Default")
      (node (ref "J1") (pin "58") (pinfunction "P6.2_58") (pintype "bidirectional"))
    )
    (net (code "136") (name "unconnected-(J1-P6.3-Pad57)") (class "Default")
      (node (ref "J1") (pin "57") (pinfunction "P6.3_57") (pintype "bidirectional"))
    )
    (net (code "137") (name "unconnected-(J1-P6.4-Pad56)") (class "Default")
      (node (ref "J1") (pin "56") (pinfunction "P6.4_56") (pintype "bidirectional"))
    )
    (net (code "138") (name "unconnected-(J1-P6.5-Pad55)") (class "Default")
      (node (ref "J1") (pin "55") (pinfunction "P6.5_55") (pintype "bidirectional"))
    )
    (net (code "139") (name "unconnected-(J1-P6.6-Pad54)") (class "Default")
      (node (ref "J1") (pin "54") (pinfunction "P6.6_54") (pintype "bidirectional"))
    )
    (net (code "140") (name "unconnected-(J1-P6.7-Pad53)") (class "Default")
      (node (ref "J1") (pin "53") (pinfunction "P6.7_53") (pintype "bidirectional"))
    )
    (net (code "141") (name "unconnected-(J1-RSVD0-Pad44)") (class "Default")
      (node (ref "J1") (pin "44") (pinfunction "RSVD0_44") (pintype "bidirectional"))
    )
    (net (code "142") (name "unconnected-(J1-RSVD1-Pad45)") (class "Default")
      (node (ref "J1") (pin "45") (pinfunction "RSVD1_45") (pintype "bidirectional"))
    )
    (net (code "143") (name "unconnected-(J1-RSVD2-Pad46)") (class "Default")
      (node (ref "J1") (pin "46") (pinfunction "RSVD2_46") (pintype "bidirectional"))
    )
    (net (code "144") (name "unconnected-(J1-RXD_MHX-Pad40)") (class "Default")
      (node (ref "J1") (pin "40") (pinfunction "RXD_MHX_40") (pintype "bidirectional"))
    )
    (net (code "145") (name "unconnected-(J1-SENSE-Pad27)") (class "Default")
      (node (ref "J1") (pin "27") (pinfunction "SENSE_27") (pintype "bidirectional"))
    )
    (net (code "146") (name "unconnected-(J1-SW0-Pad85)") (class "Default")
      (node (ref "J1") (pin "85") (pinfunction "SW0_85") (pintype "bidirectional"))
    )
    (net (code "147") (name "unconnected-(J1-SW0-Pad86)") (class "Default")
      (node (ref "J1") (pin "86") (pinfunction "SW0_86") (pintype "bidirectional"))
    )
    (net (code "148") (name "unconnected-(J1-SW1-Pad87)") (class "Default")
      (node (ref "J1") (pin "87") (pinfunction "SW1_87") (pintype "bidirectional"))
    )
    (net (code "149") (name "unconnected-(J1-SW1-Pad88)") (class "Default")
      (node (ref "J1") (pin "88") (pinfunction "SW1_88") (pintype "bidirectional"))
    )
    (net (code "150") (name "unconnected-(J1-SW2-Pad89)") (class "Default")
      (node (ref "J1") (pin "89") (pinfunction "SW2_89") (pintype "bidirectional"))
    )
    (net (code "151") (name "unconnected-(J1-SW2-Pad90)") (class "Default")
      (node (ref "J1") (pin "90") (pinfunction "SW2_90") (pintype "bidirectional"))
    )
    (net (code "152") (name "unconnected-(J1-SW3-Pad91)") (class "Default")
      (node (ref "J1") (pin "91") (pinfunction "SW3_91") (pintype "bidirectional"))
    )
    (net (code "153") (name "unconnected-(J1-SW3-Pad92)") (class "Default")
      (node (ref "J1") (pin "92") (pinfunction "SW3_92") (pintype "bidirectional"))
    )
    (net (code "154") (name "unconnected-(J1-SW4-Pad93)") (class "Default")
      (node (ref "J1") (pin "93") (pinfunction "SW4_93") (pintype "bidirectional"))
    )
    (net (code "155") (name "unconnected-(J1-SW4-Pad94)") (class "Default")
      (node (ref "J1") (pin "94") (pinfunction "SW4_94") (pintype "bidirectional"))
    )
    (net (code "156") (name "unconnected-(J1-SW5-Pad95)") (class "Default")
      (node (ref "J1") (pin "95") (pinfunction "SW5_95") (pintype "bidirectional"))
    )
    (net (code "157") (name "unconnected-(J1-SW5-Pad96)") (class "Default")
      (node (ref "J1") (pin "96") (pinfunction "SW5_96") (pintype "bidirectional"))
    )
    (net (code "158") (name "unconnected-(J1-TXD_MHX-Pad39)") (class "Default")
      (node (ref "J1") (pin "39") (pinfunction "TXD_MHX_39") (pintype "bidirectional"))
    )
    (net (code "159") (name "unconnected-(J1-USER0-Pad47)") (class "Default")
      (node (ref "J1") (pin "47") (pinfunction "USER0_47") (pintype "bidirectional"))
    )
    (net (code "160") (name "unconnected-(J1-USER1-Pad48)") (class "Default")
      (node (ref "J1") (pin "48") (pinfunction "USER1_48") (pintype "bidirectional"))
    )
    (net (code "161") (name "unconnected-(J1-USER2-Pad49)") (class "Default")
      (node (ref "J1") (pin "49") (pinfunction "USER2_49") (pintype "bidirectional"))
    )
    (net (code "162") (name "unconnected-(J1-USER3-Pad50)") (class "Default")
      (node (ref "J1") (pin "50") (pinfunction "USER3_50") (pintype "bidirectional"))
    )
    (net (code "163") (name "unconnected-(J1-USER4-Pad51)") (class "Default")
      (node (ref "J1") (pin "51") (pinfunction "USER4_51") (pintype "bidirectional"))
    )
    (net (code "164") (name "unconnected-(J1-USER5-Pad52)") (class "Default")
      (node (ref "J1") (pin "52") (pinfunction "USER5_52") (pintype "bidirectional"))
    )
    (net (code "165") (name "unconnected-(J1-USER6-Pad99)") (class "Default")
      (node (ref "J1") (pin "99") (pinfunction "USER6_99") (pintype "bidirectional"))
    )
    (net (code "166") (name "unconnected-(J1-USER7-Pad100)") (class "Default")
      (node (ref "J1") (pin "100") (pinfunction "USER7_100") (pintype "bidirectional"))
    )
    (net (code "167") (name "unconnected-(J1-USER8-Pad101)") (class "Default")
      (node (ref "J1") (pin "101") (pinfunction "USER8_101") (pintype "bidirectional"))
    )
    (net (code "168") (name "unconnected-(J1-USER9-Pad102)") (class "Default")
      (node (ref "J1") (pin "102") (pinfunction "USER9_102") (pintype "bidirectional"))
    )
    (net (code "169") (name "unconnected-(J1-USER10-Pad103)") (class "Default")
      (node (ref "J1") (pin "103") (pinfunction "USER10_103") (pintype "bidirectional"))
    )
    (net (code "170") (name "unconnected-(J1-USER11-Pad104)") (class "Default")
      (node (ref "J1") (pin "104") (pinfunction "USER11_104") (pintype "bidirectional"))
    )
    (net (code "171") (name "unconnected-(J1-VBACKUP-Pad42)") (class "Default")
      (node (ref "J1") (pin "42") (pinfunction "VBACKUP_42") (pintype "bidirectional"))
    )
    (net (code "172") (name "unconnected-(J1-VBATT-Pad97)") (class "Default")
      (node (ref "J1") (pin "97") (pinfunction "VBATT_97") (pintype "bidirectional"))
    )
    (net (code "173") (name "unconnected-(J1-VBATT-Pad98)") (class "Default")
      (node (ref "J1") (pin "98") (pinfunction "VBATT_98") (pintype "bidirectional"))
    )
    (net (code "174") (name "unconnected-(J1-VCC_SYS-Pad79)") (class "Default")
      (node (ref "J1") (pin "79") (pinfunction "VCC_SYS_79") (pintype "bidirectional"))
    )
    (net (code "175") (name "unconnected-(J1-VCC_SYS-Pad80)") (class "Default")
      (node (ref "J1") (pin "80") (pinfunction "VCC_SYS_80") (pintype "bidirectional"))
    )
    (net (code "176") (name "unconnected-(J1-VEREF+-Pad28)") (class "Default")
      (node (ref "J1") (pin "28") (pinfunction "VEREF+_28") (pintype "bidirectional"))
    )
    (net (code "177") (name "unconnected-(J1-VREF+-Pad26)") (class "Default")
      (node (ref "J1") (pin "26") (pinfunction "VREF+_26") (pintype "bidirectional"))
    )
    (net (code "178") (name "unconnected-(J1-VREF--Pad30)") (class "Default")
      (node (ref "J1") (pin "30") (pinfunction "VREF-_30") (pintype "bidirectional"))
    )
    (net (code "179") (name "unconnected-(J4-Pad2)") (class "Default")
      (node (ref "J4") (pin "2") (pinfunction "2_2") (pintype "bidirectional"))
    )
    (net (code "180") (name "unconnected-(J4-Pad5)") (class "Default")
      (node (ref "J4") (pin "5") (pinfunction "5_5") (pintype "bidirectional"))
    )
    (net (code "181") (name "unconnected-(J4-Pad9)") (class "Default")
      (node (ref "J4") (pin "9") (pinfunction "9_9") (pintype "bidirectional"))
    )
    (net (code "182") (name "unconnected-(J4-Pad12)") (class "Default")
      (node (ref "J4") (pin "12") (pinfunction "12_12") (pintype "bidirectional"))
    )
    (net (code "183") (name "unconnected-(J5-Pad2)") (class "Default")
      (node (ref "J5") (pin "2") (pinfunction "2_2") (pintype "bidirectional"))
    )
    (net (code "184") (name "unconnected-(J5-Pad5)") (class "Default")
      (node (ref "J5") (pin "5") (pinfunction "5_5") (pintype "bidirectional"))
    )
    (net (code "185") (name "unconnected-(J5-Pad9)") (class "Default")
      (node (ref "J5") (pin "9") (pinfunction "9_9") (pintype "bidirectional"))
    )
    (net (code "186") (name "unconnected-(J5-Pad12)") (class "Default")
      (node (ref "J5") (pin "12") (pinfunction "12_12") (pintype "bidirectional"))
    )
    (net (code "187") (name "unconnected-(OK1-A2-Pad3)") (class "Default")
      (node (ref "OK1") (pin "3") (pinfunction "A2_3") (pintype "bidirectional"))
    )
    (net (code "188") (name "unconnected-(OK1-A3-Pad5)") (class "Default")
      (node (ref "OK1") (pin "5") (pinfunction "A3_5") (pintype "bidirectional"))
    )
    (net (code "189") (name "unconnected-(OK1-A4-Pad7)") (class "Default")
      (node (ref "OK1") (pin "7") (pinfunction "A4_7") (pintype "bidirectional"))
    )
    (net (code "190") (name "unconnected-(OK1-C2-Pad14)") (class "Default")
      (node (ref "OK1") (pin "14") (pinfunction "C2_14") (pintype "bidirectional"))
    )
    (net (code "191") (name "unconnected-(OK1-C3-Pad12)") (class "Default")
      (node (ref "OK1") (pin "12") (pinfunction "C3_12") (pintype "bidirectional"))
    )
    (net (code "192") (name "unconnected-(OK1-C4-Pad10)") (class "Default")
      (node (ref "OK1") (pin "10") (pinfunction "C4_10") (pintype "bidirectional"))
    )
    (net (code "193") (name "unconnected-(OK1-E2-Pad13)") (class "Default")
      (node (ref "OK1") (pin "13") (pinfunction "E2_13") (pintype "bidirectional"))
    )
    (net (code "194") (name "unconnected-(OK1-E3-Pad11)") (class "Default")
      (node (ref "OK1") (pin "11") (pinfunction "E3_11") (pintype "bidirectional"))
    )
    (net (code "195") (name "unconnected-(OK1-E4-Pad9)") (class "Default")
      (node (ref "OK1") (pin "9") (pinfunction "E4_9") (pintype "bidirectional"))
    )
    (net (code "196") (name "unconnected-(OK1-K2-Pad4)") (class "Default")
      (node (ref "OK1") (pin "4") (pinfunction "K2_4") (pintype "bidirectional"))
    )
    (net (code "197") (name "unconnected-(OK1-K3-Pad6)") (class "Default")
      (node (ref "OK1") (pin "6") (pinfunction "K3_6") (pintype "bidirectional"))
    )
    (net (code "198") (name "unconnected-(OK1-K4-Pad8)") (class "Default")
      (node (ref "OK1") (pin "8") (pinfunction "K4_8") (pintype "bidirectional"))
    )
    (net (code "199") (name "unconnected-(U1-COMP-PadB7)") (class "Default")
      (node (ref "U1") (pin "B7") (pinfunction "COMP_B7") (pintype "bidirectional"))
    )
    (net (code "200") (name "unconnected-(U1-EXTV_CC-PadF6)") (class "Default")
      (node (ref "U1") (pin "F6") (pinfunction "EXTV_CC_F6") (pintype "bidirectional"))
    )
    (net (code "201") (name "unconnected-(U1-PLLIN-PadB9)") (class "Default")
      (node (ref "U1") (pin "B9") (pinfunction "PLLIN_B9") (pintype "bidirectional"))
    )
    (net (code "202") (name "unconnected-(U1-SS-PadA6)") (class "Default")
      (node (ref "U1") (pin "A6") (pinfunction "SS_A6") (pintype "bidirectional"))
    )
    (net (code "203") (name "unconnected-(U1-STBYMD-PadA10)") (class "Default")
      (node (ref "U1") (pin "A10") (pinfunction "STBYMD_A10") (pintype "bidirectional"))
    )
    (net (code "204") (name "unconnected-(U2-ADC_IN0-Pad2)") (class "Default")
      (node (ref "U2") (pin "2") (pinfunction "ADC_IN0_2") (pintype "bidirectional"))
    )
    (net (code "205") (name "unconnected-(U2-ADC_IN1-Pad1)") (class "Default")
      (node (ref "U2") (pin "1") (pinfunction "ADC_IN1_1") (pintype "bidirectional"))
    )
    (net (code "206") (name "unconnected-(U2-ADC_IN2-Pad4)") (class "Default")
      (node (ref "U2") (pin "4") (pinfunction "ADC_IN2_4") (pintype "bidirectional"))
    )
    (net (code "207") (name "unconnected-(U2-ADC_IN3-Pad3)") (class "Default")
      (node (ref "U2") (pin "3") (pinfunction "ADC_IN3_3") (pintype "bidirectional"))
    )
    (net (code "208") (name "unconnected-(U2-ADC_IN4-Pad6)") (class "Default")
      (node (ref "U2") (pin "6") (pinfunction "ADC_IN4_6") (pintype "bidirectional"))
    )
    (net (code "209") (name "unconnected-(U2-ADC_IN7-Pad5)") (class "Default")
      (node (ref "U2") (pin "5") (pinfunction "ADC_IN7_5") (pintype "bidirectional"))
    )
    (net (code "210") (name "unconnected-(U2-AGND-Pad8)") (class "Default")
      (node (ref "U2") (pin "8") (pinfunction "AGND_8") (pintype "bidirectional"))
    )
    (net (code "211") (name "unconnected-(U2-CAN1_RX-Pad20)") (class "Default")
      (node (ref "U2") (pin "20") (pinfunction "CAN1_RX_20") (pintype "bidirectional"))
    )
    (net (code "212") (name "unconnected-(U2-CAN1_TX-Pad22)") (class "Default")
      (node (ref "U2") (pin "22") (pinfunction "CAN1_TX_22") (pintype "bidirectional"))
    )
    (net (code "213") (name "unconnected-(U2-ERX_JM-Pad44)") (class "Default")
      (node (ref "U2") (pin "44") (pinfunction "ERX_JM_44") (pintype "bidirectional"))
    )
    (net (code "214") (name "unconnected-(U2-ERX_JP-Pad43)") (class "Default")
      (node (ref "U2") (pin "43") (pinfunction "ERX_JP_43") (pintype "bidirectional"))
    )
    (net (code "215") (name "unconnected-(U2-ETX_JM-Pad46)") (class "Default")
      (node (ref "U2") (pin "46") (pinfunction "ETX_JM_46") (pintype "bidirectional"))
    )
    (net (code "216") (name "unconnected-(U2-ETX_JP-Pad45)") (class "Default")
      (node (ref "U2") (pin "45") (pinfunction "ETX_JP_45") (pintype "bidirectional"))
    )
    (net (code "217") (name "unconnected-(U2-IRQ2-Pad50)") (class "Default")
      (node (ref "U2") (pin "50") (pinfunction "IRQ2_50") (pintype "bidirectional"))
    )
    (net (code "218") (name "unconnected-(U2-IRQ3-Pad49)") (class "Default")
      (node (ref "U2") (pin "49") (pinfunction "IRQ3_49") (pintype "bidirectional"))
    )
    (net (code "219") (name "unconnected-(U2-IRQ7-Pad9)") (class "Default")
      (node (ref "U2") (pin "9") (pinfunction "IRQ7_9") (pintype "bidirectional"))
    )
    (net (code "220") (name "unconnected-(U2-LINKLED-Pad42)") (class "Default")
      (node (ref "U2") (pin "42") (pinfunction "LINKLED_42") (pintype "bidirectional"))
    )
    (net (code "221") (name "unconnected-(U2-OW_DAT-Pad12)") (class "Default")
      (node (ref "U2") (pin "12") (pinfunction "OW_DAT_12") (pintype "bidirectional"))
    )
    (net (code "222") (name "unconnected-(U2-RSTI-Pad11)") (class "Default")
      (node (ref "U2") (pin "11") (pinfunction "RSTI_11") (pintype "bidirectional"))
    )
    (net (code "223") (name "unconnected-(U2-SDHC_DAT3-Pad15)") (class "Default")
      (node (ref "U2") (pin "15") (pinfunction "SDHC_DAT3_15") (pintype "bidirectional"))
    )
    (net (code "224") (name "unconnected-(U2-SPEEDLED-Pad40)") (class "Default")
      (node (ref "U2") (pin "40") (pinfunction "SPEEDLED_40") (pintype "bidirectional"))
    )
    (net (code "225") (name "unconnected-(U2-T0IN-Pad19)") (class "Default")
      (node (ref "U2") (pin "19") (pinfunction "T0IN_19") (pintype "bidirectional"))
    )
    (net (code "226") (name "unconnected-(U2-T1IN-Pad21)") (class "Default")
      (node (ref "U2") (pin "21") (pinfunction "T1IN_21") (pintype "bidirectional"))
    )
    (net (code "227") (name "unconnected-(U2-T3IN-Pad25)") (class "Default")
      (node (ref "U2") (pin "25") (pinfunction "T3IN_25") (pintype "bidirectional"))
    )
    (net (code "228") (name "unconnected-(U2-UART0_CTS-Pad30)") (class "Default")
      (node (ref "U2") (pin "30") (pinfunction "UART0_CTS_30") (pintype "bidirectional"))
    )
    (net (code "229") (name "unconnected-(U2-UART0_RTS-Pad28)") (class "Default")
      (node (ref "U2") (pin "28") (pinfunction "UART0_RTS_28") (pintype "bidirectional"))
    )
    (net (code "230") (name "unconnected-(U2-UART2_CTS-Pad10)") (class "Default")
      (node (ref "U2") (pin "10") (pinfunction "UART2_CTS_10") (pintype "bidirectional"))
    )
    (net (code "231") (name "unconnected-(U2-UART2_RTS-Pad14)") (class "Default")
      (node (ref "U2") (pin "14") (pinfunction "UART2_RTS_14") (pintype "bidirectional"))
    )
    (net (code "232") (name "unconnected-(U2-UART2_RX-Pad13)") (class "Default")
      (node (ref "U2") (pin "13") (pinfunction "UART2_RX_13") (pintype "bidirectional"))
    )
    (net (code "233") (name "unconnected-(U2-UART2_TX-Pad16)") (class "Default")
      (node (ref "U2") (pin "16") (pinfunction "UART2_TX_16") (pintype "bidirectional"))
    )
    (net (code "234") (name "unconnected-(U2-USBO_DM-Pad51)") (class "Default")
      (node (ref "U2") (pin "51") (pinfunction "USBO_DM_51") (pintype "bidirectional"))
    )
    (net (code "235") (name "unconnected-(U2-USBO_DP-Pad52)") (class "Default")
      (node (ref "U2") (pin "52") (pinfunction "USBO_DP_52") (pintype "bidirectional"))
    )
    (net (code "236") (name "unconnected-(U2-VCC3VE-Pad41)") (class "Default")
      (node (ref "U2") (pin "41") (pinfunction "VCC3VE_41") (pintype "bidirectional"))
    )
    (net (code "237") (name "unconnected-(U2-VDDA_DAC_ADC-Pad7)") (class "Default")
      (node (ref "U2") (pin "7") (pinfunction "VDDA_DAC_ADC_7") (pintype "bidirectional"))
    )
    (net (code "238") (name "unconnected-(U3-TIMER1-Pad2)") (class "Default")
      (node (ref "U3") (pin "2") (pinfunction "TIMER1_2") (pintype "bidirectional"))
    )
    (net (code "239") (name "unconnected-(U3-TIMER2-Pad4)") (class "Default")
      (node (ref "U3") (pin "4") (pinfunction "TIMER2_4") (pintype "bidirectional"))
    )
    (net (code "240") (name "unconnected-(U3-TIMER3-Pad6)") (class "Default")
      (node (ref "U3") (pin "6") (pinfunction "TIMER3_6") (pintype "bidirectional"))
    )
    (net (code "241") (name "unconnected-(U3-TIMER4-Pad8)") (class "Default")
      (node (ref "U3") (pin "8") (pinfunction "TIMER4_8") (pintype "bidirectional"))
    )
    (net (code "242") (name "unconnected-(U4-TIMER1-Pad2)") (class "Default")
      (node (ref "U4") (pin "2") (pinfunction "TIMER1_2") (pintype "bidirectional"))
    )
    (net (code "243") (name "unconnected-(U4-TIMER2-Pad4)") (class "Default")
      (node (ref "U4") (pin "4") (pinfunction "TIMER2_4") (pintype "bidirectional"))
    )
    (net (code "244") (name "unconnected-(U4-TIMER3-Pad6)") (class "Default")
      (node (ref "U4") (pin "6") (pinfunction "TIMER3_6") (pintype "bidirectional"))
    )
    (net (code "245") (name "unconnected-(U4-TIMER4-Pad8)") (class "Default")
      (node (ref "U4") (pin "8") (pinfunction "TIMER4_8") (pintype "bidirectional"))
    )
  )
)
